# tool-board-atmega.net
KiCad netlist of a schematic drawn in EAGLE
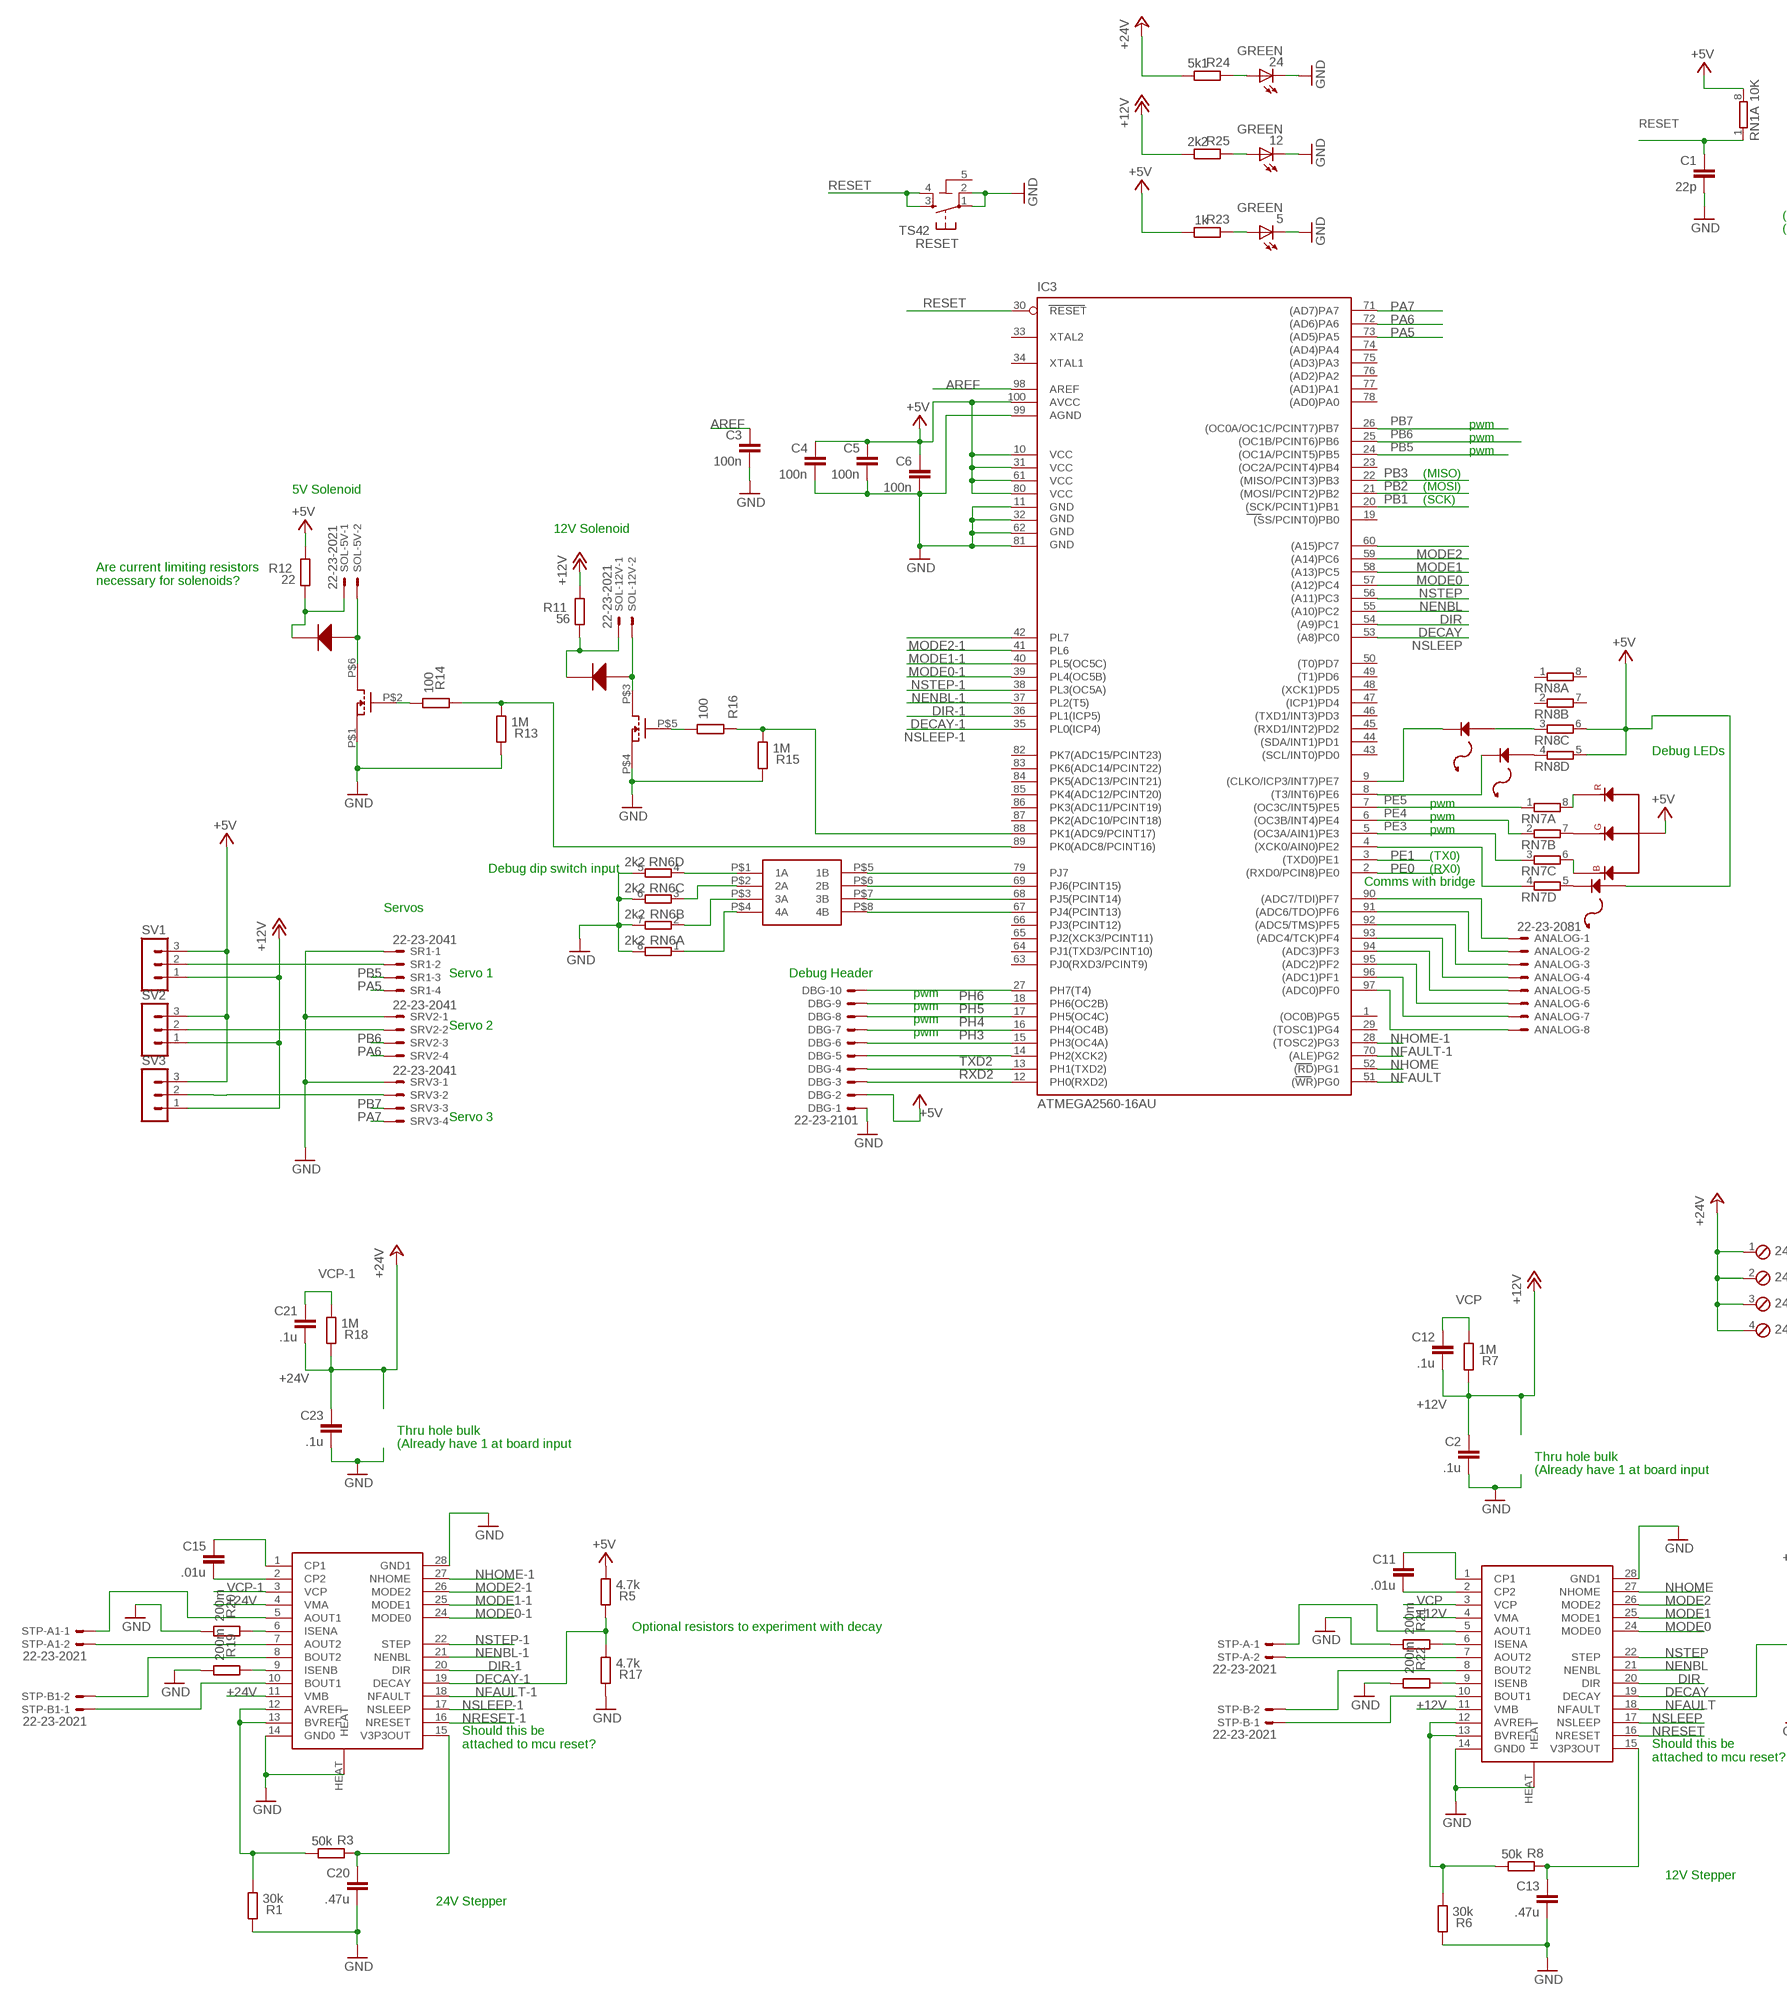
[diagram p0: schematic, sheet 1, part 1 of 2]
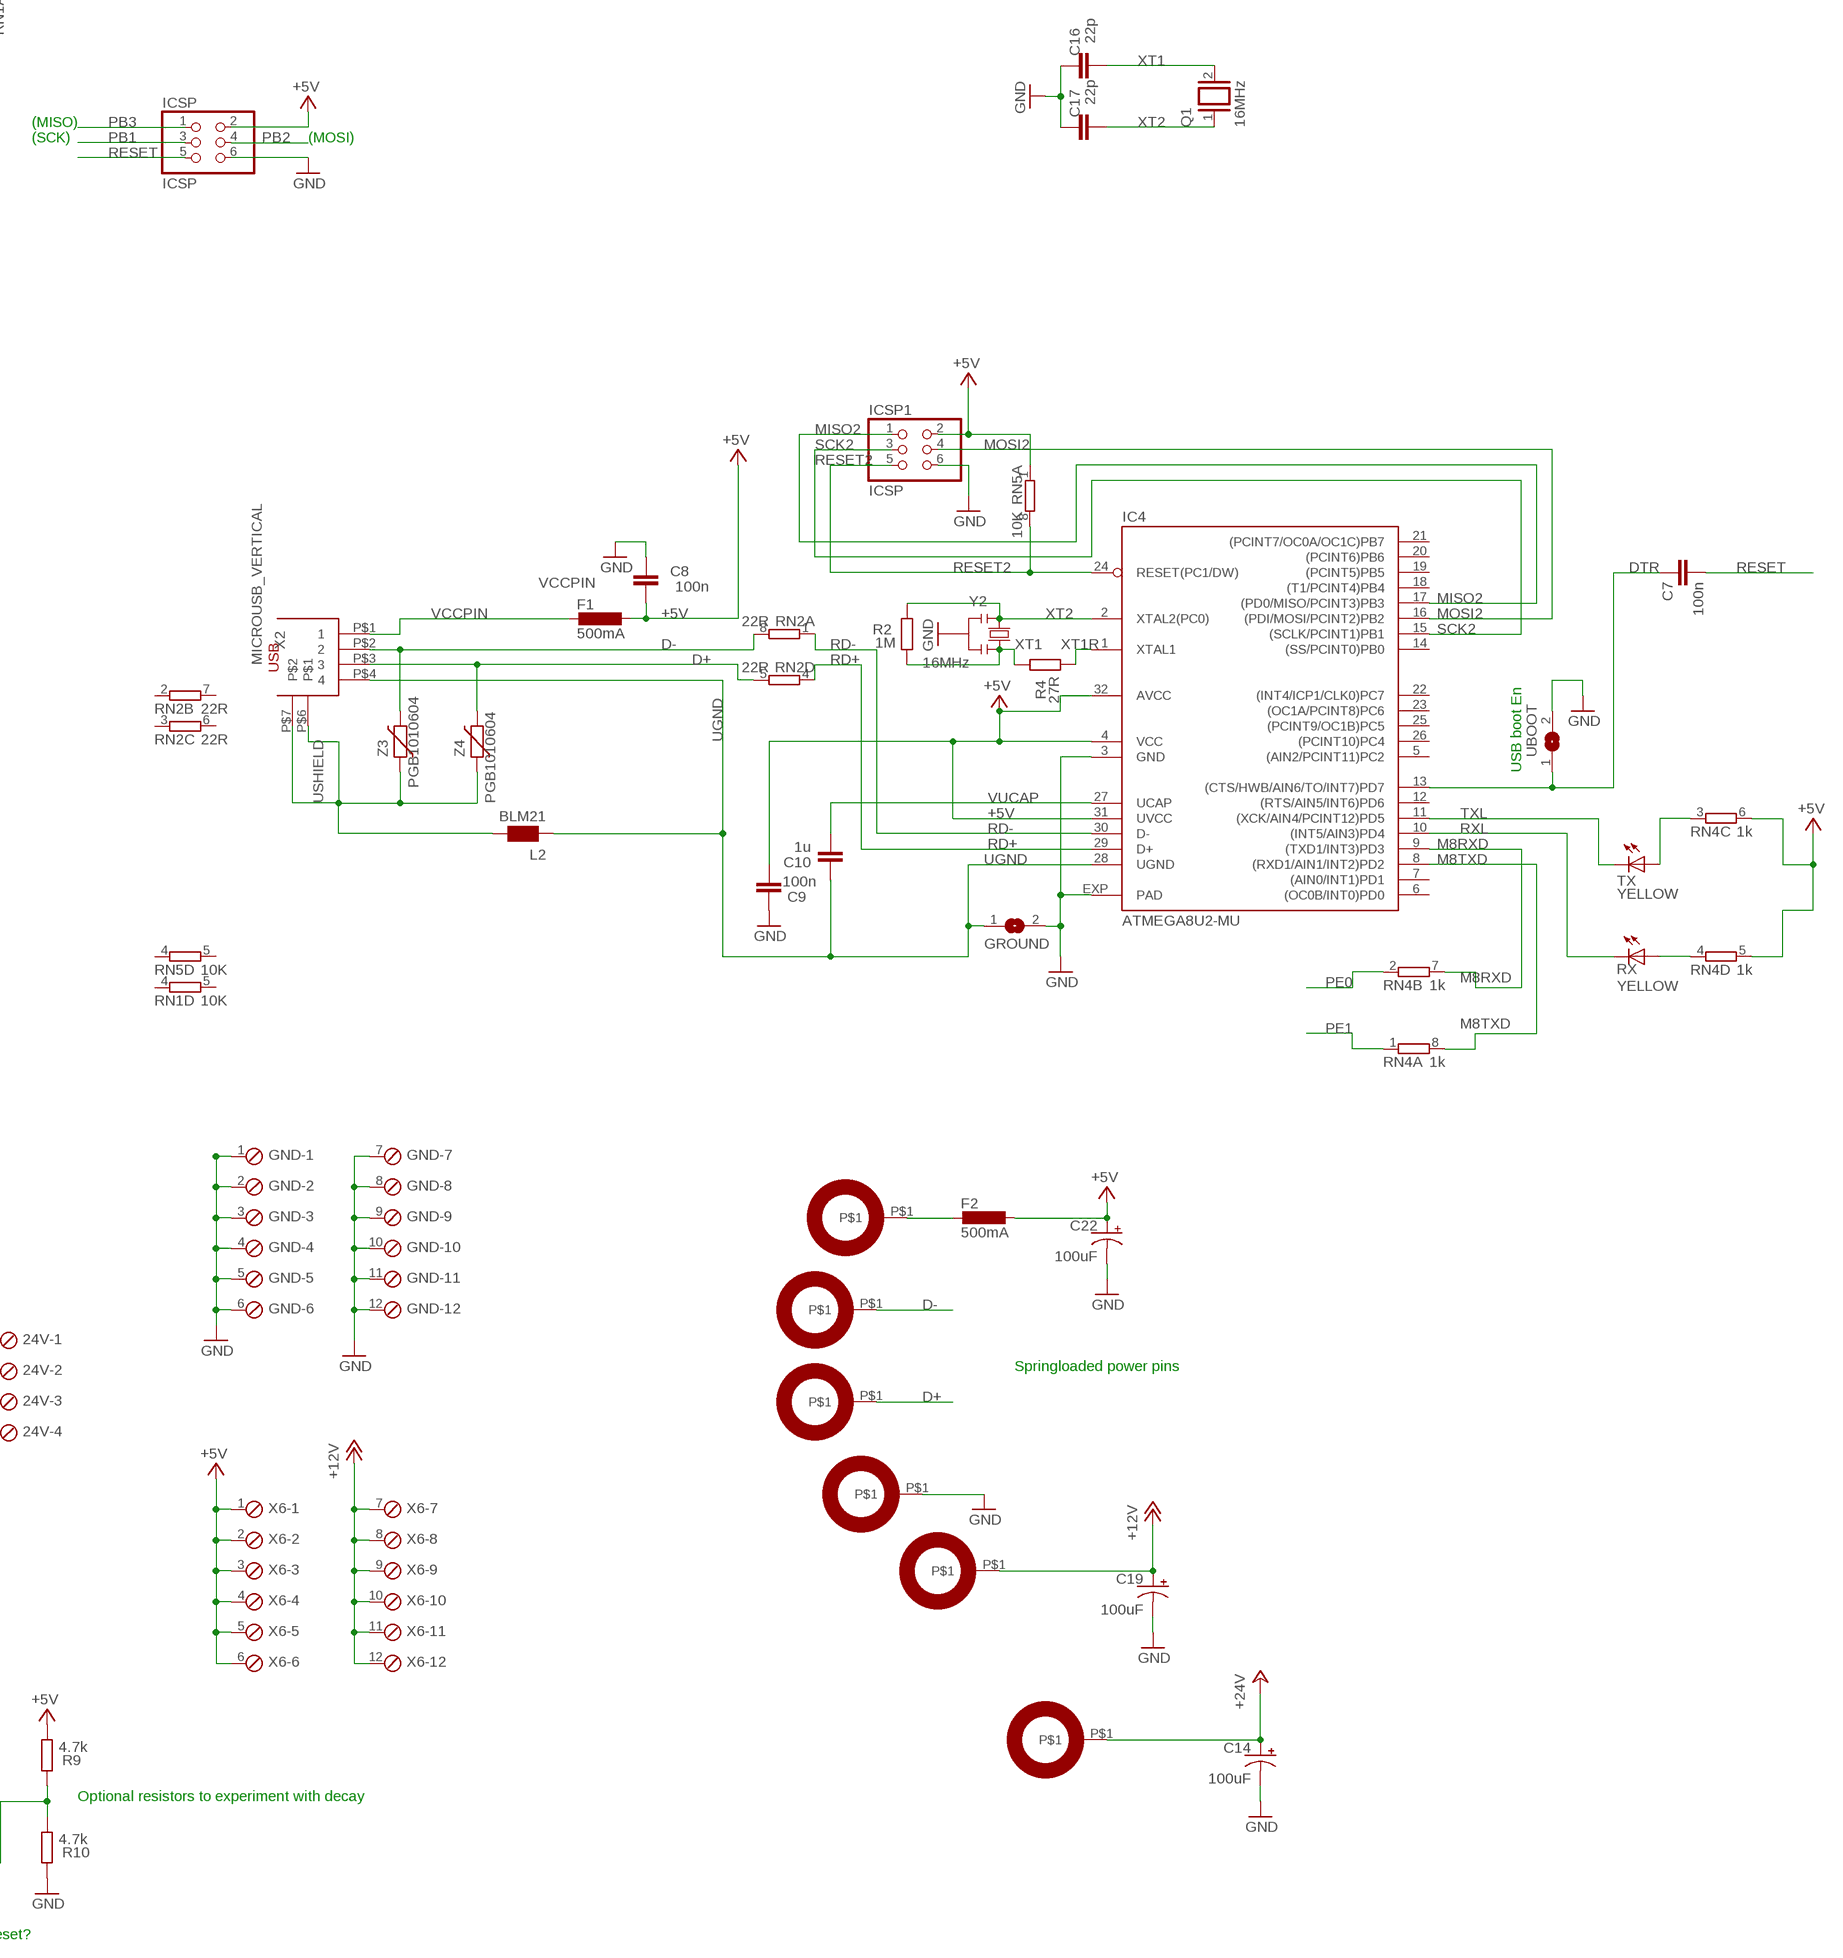
[diagram p1: schematic, sheet 1, part 2 of 2]

(export (version "E")
  (design (tool "Eeschema 10.0.6"))
  (components
    (comp (ref "5")
      (value "GREEN")
      (footprint "eagle-import:CHIP-LED0805")
      (libsource (lib "eagle-import") (part "LEDCHIP-LED0805"))
    )
    (comp (ref "12")
      (value "GREEN")
      (footprint "eagle-import:CHIP-LED0805")
      (libsource (lib "eagle-import") (part "LEDCHIP-LED0805"))
    )
    (comp (ref "24")
      (value "GREEN")
      (footprint "eagle-import:CHIP-LED0805")
      (libsource (lib "eagle-import") (part "LEDCHIP-LED0805"))
    )
    (comp (ref "24V")
      (value "MPT4")
      (footprint "eagle-import:4POL254")
      (libsource (lib "eagle-import") (part "MPT4"))
    )
    (comp (ref "ANALOG")
      (value "22-23-2081")
      (footprint "eagle-import:22-23-2081")
      (fields (field (name "MF") "MOLEX"))
      (libsource (lib "eagle-import") (part "22-23-2081"))
    )
    (comp (ref "C1")
      (value "22p")
      (footprint "eagle-import:C0603-ROUND")
      (libsource (lib "eagle-import") (part "C-EU0603-RND"))
    )
    (comp (ref "C2")
      (value ".1u")
      (footprint "eagle-import:C0603-ROUND")
      (libsource (lib "eagle-import") (part "C-EU0603-RND"))
    )
    (comp (ref "C3")
      (value "100n")
      (footprint "eagle-import:C0603-ROUND")
      (libsource (lib "eagle-import") (part "C-EU0603-RND"))
    )
    (comp (ref "C4")
      (value "100n")
      (footprint "eagle-import:C0603-ROUND")
      (libsource (lib "eagle-import") (part "C-EU0603-RND"))
    )
    (comp (ref "C5")
      (value "100n")
      (footprint "eagle-import:C0603-ROUND")
      (libsource (lib "eagle-import") (part "C-EU0603-RND"))
    )
    (comp (ref "C6")
      (value "100n")
      (footprint "eagle-import:C0603-ROUND")
      (libsource (lib "eagle-import") (part "C-EU0603-RND"))
    )
    (comp (ref "C7")
      (value "100n")
      (footprint "eagle-import:C0603-ROUND")
      (libsource (lib "eagle-import") (part "C-EU0603-RND"))
    )
    (comp (ref "C8")
      (value "100n")
      (footprint "eagle-import:C0603")
      (libsource (lib "eagle-import") (part "rcl_C-EUC0603"))
    )
    (comp (ref "C9")
      (value "100n")
      (footprint "eagle-import:C0603-ROUND")
      (libsource (lib "eagle-import") (part "C-EU0603-RND"))
    )
    (comp (ref "C10")
      (value "1u")
      (footprint "eagle-import:C0603-ROUND")
      (libsource (lib "eagle-import") (part "C-EU0603-RND"))
    )
    (comp (ref "C11")
      (value ".01u")
      (footprint "eagle-import:C0603-ROUND")
      (libsource (lib "eagle-import") (part "C-EU0603-RND"))
    )
    (comp (ref "C12")
      (value ".1u")
      (footprint "eagle-import:C0603-ROUND")
      (libsource (lib "eagle-import") (part "C-EU0603-RND"))
    )
    (comp (ref "C13")
      (value ".47u")
      (footprint "eagle-import:C0603-ROUND")
      (libsource (lib "eagle-import") (part "C-EU0603-RND"))
    )
    (comp (ref "C14")
      (value "100uF")
      (footprint "eagle-import:E3,5-8")
      (libsource (lib "eagle-import") (part "CPOL-USE3.5-8"))
    )
    (comp (ref "C15")
      (value ".01u")
      (footprint "eagle-import:C0603-ROUND")
      (libsource (lib "eagle-import") (part "C-EU0603-RND"))
    )
    (comp (ref "C16")
      (value "22p")
      (footprint "eagle-import:C0603-ROUND")
      (libsource (lib "eagle-import") (part "C-EU0603-RND"))
    )
    (comp (ref "C17")
      (value "22p")
      (footprint "eagle-import:C0603-ROUND")
      (libsource (lib "eagle-import") (part "C-EU0603-RND"))
    )
    (comp (ref "C19")
      (value "100uF")
      (footprint "eagle-import:E3,5-8")
      (libsource (lib "eagle-import") (part "CPOL-USE3.5-8"))
    )
    (comp (ref "C20")
      (value ".47u")
      (footprint "eagle-import:C0603-ROUND")
      (libsource (lib "eagle-import") (part "C-EU0603-RND"))
    )
    (comp (ref "C21")
      (value ".1u")
      (footprint "eagle-import:C0603-ROUND")
      (libsource (lib "eagle-import") (part "C-EU0603-RND"))
    )
    (comp (ref "C22")
      (value "100uF")
      (footprint "eagle-import:E3,5-8")
      (libsource (lib "eagle-import") (part "CPOL-USE3.5-8"))
    )
    (comp (ref "C23")
      (value ".1u")
      (footprint "eagle-import:C0603-ROUND")
      (libsource (lib "eagle-import") (part "C-EU0603-RND"))
    )
    (comp (ref "DBG")
      (value "22-23-2101")
      (footprint "eagle-import:22-23-2101")
      (fields (field (name "MF") "MOLEX"))
      (libsource (lib "eagle-import") (part "22-23-2101"))
    )
    (comp (ref "F1")
      (value "500mA")
      (footprint "eagle-import:L1812")
      (libsource (lib "eagle-import") (part "L-EUL1812"))
    )
    (comp (ref "F2")
      (value "500mA")
      (footprint "eagle-import:L1812")
      (libsource (lib "eagle-import") (part "L-EUL1812"))
    )
    (comp (ref "GND")
      (value "MPT12")
      (footprint "eagle-import:12POL254")
      (libsource (lib "eagle-import") (part "MPT12"))
    )
    (comp (ref "GROUND")
      (value "SJ")
      (footprint "eagle-import:SJ")
      (libsource (lib "eagle-import") (part "SJ"))
    )
    (comp (ref "IC3")
      (value "ATMEGA2560-16AU")
      (footprint "eagle-import:TQFP100")
      (libsource (lib "eagle-import") (part "ATMEGAAU1280-16"))
    )
    (comp (ref "IC4")
      (value "ATMEGA8U2-MU")
      (footprint "eagle-import:QFN32")
      (libsource (lib "eagle-import") (part "ATMEGA8U2-MU"))
    )
    (comp (ref "ICSP")
      (value "ICSP")
      (footprint "eagle-import:2X03")
      (libsource (lib "eagle-import") (part "PINHD-2X3"))
    )
    (comp (ref "ICSP1")
      (value "ICSP")
      (footprint "eagle-import:2X03")
      (libsource (lib "eagle-import") (part "PINHD-2X3"))
    )
    (comp (ref "L2")
      (value "BLM21")
      (footprint "eagle-import:0805")
      (libsource (lib "eagle-import") (part "WE-CBF_0805"))
    )
    (comp (ref "Q1")
      (value "16MHz")
      (footprint "eagle-import:QS")
      (libsource (lib "eagle-import") (part "XTAL/S"))
    )
    (comp (ref "R1")
      (value "30k")
      (footprint "eagle-import:R0603-ROUND")
      (libsource (lib "eagle-import") (part "R-EU_R0603"))
    )
    (comp (ref "R2")
      (value "1M")
      (footprint "eagle-import:R0603-ROUND")
      (libsource (lib "eagle-import") (part "R-EU_R0603"))
    )
    (comp (ref "R3")
      (value "50k")
      (footprint "eagle-import:R0603-ROUND")
      (libsource (lib "eagle-import") (part "R-EU_R0603"))
    )
    (comp (ref "R4")
      (value "27R")
      (footprint "eagle-import:R0603-ROUND")
      (libsource (lib "eagle-import") (part "R-EU_R0603"))
    )
    (comp (ref "R5")
      (value "4.7k")
      (footprint "eagle-import:R0603-ROUND")
      (libsource (lib "eagle-import") (part "R-EU_R0603"))
    )
    (comp (ref "R6")
      (value "30k")
      (footprint "eagle-import:R0603-ROUND")
      (libsource (lib "eagle-import") (part "R-EU_R0603"))
    )
    (comp (ref "R7")
      (value "1M")
      (footprint "eagle-import:R0603-ROUND")
      (libsource (lib "eagle-import") (part "R-EU_R0603"))
    )
    (comp (ref "R8")
      (value "50k")
      (footprint "eagle-import:R0603-ROUND")
      (libsource (lib "eagle-import") (part "R-EU_R0603"))
    )
    (comp (ref "R9")
      (value "4.7k")
      (footprint "eagle-import:R0603-ROUND")
      (libsource (lib "eagle-import") (part "R-EU_R0603"))
    )
    (comp (ref "R10")
      (value "4.7k")
      (footprint "eagle-import:R0603-ROUND")
      (libsource (lib "eagle-import") (part "R-EU_R0603"))
    )
    (comp (ref "R11")
      (value "56")
      (footprint "eagle-import:R0603-ROUND")
      (libsource (lib "eagle-import") (part "R-EU_R0603"))
    )
    (comp (ref "R12")
      (value "22")
      (footprint "eagle-import:R0603-ROUND")
      (libsource (lib "eagle-import") (part "R-EU_R0603"))
    )
    (comp (ref "R13")
      (value "1M")
      (footprint "eagle-import:R0603-ROUND")
      (libsource (lib "eagle-import") (part "R-EU_R0603"))
    )
    (comp (ref "R14")
      (value "100")
      (footprint "eagle-import:R0603-ROUND")
      (libsource (lib "eagle-import") (part "R-EU_R0603"))
    )
    (comp (ref "R15")
      (value "1M")
      (footprint "eagle-import:SMARTPRJ_R0603-ROUND")
      (libsource (lib "eagle-import") (part "SMARTPRJ_R-EU_0603-RND"))
    )
    (comp (ref "R16")
      (value "100")
      (footprint "eagle-import:R0603-ROUND")
      (libsource (lib "eagle-import") (part "R-EU_R0603"))
    )
    (comp (ref "R17")
      (value "4.7k")
      (footprint "eagle-import:R0603-ROUND")
      (libsource (lib "eagle-import") (part "R-EU_R0603"))
    )
    (comp (ref "R18")
      (value "1M")
      (footprint "eagle-import:R0603-ROUND")
      (libsource (lib "eagle-import") (part "R-EU_R0603"))
    )
    (comp (ref "R19")
      (value "200m")
      (footprint "eagle-import:R0603-ROUND")
      (libsource (lib "eagle-import") (part "R-EU_R0603"))
    )
    (comp (ref "R20")
      (value "200m")
      (footprint "eagle-import:R0603-ROUND")
      (libsource (lib "eagle-import") (part "R-EU_R0603"))
    )
    (comp (ref "R21")
      (value "200m")
      (footprint "eagle-import:R0603-ROUND")
      (libsource (lib "eagle-import") (part "R-EU_R0603"))
    )
    (comp (ref "R22")
      (value "200m")
      (footprint "eagle-import:R0603-ROUND")
      (libsource (lib "eagle-import") (part "R-EU_R0603"))
    )
    (comp (ref "R23")
      (value "1k")
      (footprint "eagle-import:R0603-ROUND")
      (libsource (lib "eagle-import") (part "R-EU_R0603"))
    )
    (comp (ref "R24")
      (value "5k1")
      (footprint "eagle-import:R0603-ROUND")
      (libsource (lib "eagle-import") (part "R-EU_R0603"))
    )
    (comp (ref "R25")
      (value "2k2")
      (footprint "eagle-import:R0603-ROUND")
      (libsource (lib "eagle-import") (part "R-EU_R0603"))
    )
    (comp (ref "RESET")
      (value "TS42")
      (footprint "eagle-import:TS42")
      (libsource (lib "eagle-import") (part "TS42"))
    )
    (comp (ref "RN1")
      (value "10K")
      (footprint "eagle-import:CAT16")
      (libsource (lib "eagle-import") (part "4R-NCAT16"))
    )
    (comp (ref "RN2")
      (value "22R")
      (footprint "eagle-import:CAY16")
      (libsource (lib "eagle-import") (part "4R-NCAY16"))
    )
    (comp (ref "RN4")
      (value "1k")
      (footprint "eagle-import:CAY16")
      (libsource (lib "eagle-import") (part "4R-NCAY16"))
    )
    (comp (ref "RN5")
      (value "10K")
      (footprint "eagle-import:CAT16")
      (libsource (lib "eagle-import") (part "4R-NCAT16"))
    )
    (comp (ref "RN6")
      (value "2k2")
      (footprint "eagle-import:CAY16")
      (libsource (lib "eagle-import") (part "resistor-dil_342_4R-NCAY16"))
    )
    (comp (ref "RN7")
      (value "4R-NCAY16")
      (footprint "eagle-import:CAY16")
      (libsource (lib "eagle-import") (part "resistor-dil_342_4R-NCAY16"))
    )
    (comp (ref "RN8")
      (value "4R-NCAY16")
      (footprint "eagle-import:CAY16")
      (libsource (lib "eagle-import") (part "resistor-dil_342_4R-NCAY16"))
    )
    (comp (ref "RX")
      (value "YELLOW")
      (footprint "eagle-import:CHIP-LED0805")
      (libsource (lib "eagle-import") (part "LEDCHIP-LED0805"))
    )
    (comp (ref "SOL-5V")
      (value "22-23-2021")
      (footprint "eagle-import:22-23-2021")
      (fields (field (name "MF") "MOLEX"))
      (libsource (lib "eagle-import") (part "22-23-2021"))
    )
    (comp (ref "SOL-12V")
      (value "22-23-2021")
      (footprint "eagle-import:22-23-2021")
      (fields (field (name "MF") "MOLEX"))
      (libsource (lib "eagle-import") (part "22-23-2021"))
    )
    (comp (ref "SR1")
      (value "22-23-2041")
      (footprint "eagle-import:22-23-2041")
      (fields (field (name "MF") "MOLEX"))
      (libsource (lib "eagle-import") (part "22-23-2041"))
    )
    (comp (ref "SRV2")
      (value "22-23-2041")
      (footprint "eagle-import:22-23-2041")
      (fields (field (name "MF") "MOLEX"))
      (libsource (lib "eagle-import") (part "22-23-2041"))
    )
    (comp (ref "SRV3")
      (value "22-23-2041")
      (footprint "eagle-import:22-23-2041")
      (fields (field (name "MF") "MOLEX"))
      (libsource (lib "eagle-import") (part "22-23-2041"))
    )
    (comp (ref "STP-A")
      (value "22-23-2021")
      (footprint "eagle-import:22-23-2021")
      (fields (field (name "MF") "MOLEX"))
      (libsource (lib "eagle-import") (part "22-23-2021"))
    )
    (comp (ref "STP-A1")
      (value "22-23-2021")
      (footprint "eagle-import:22-23-2021")
      (fields (field (name "MF") "MOLEX"))
      (libsource (lib "eagle-import") (part "22-23-2021"))
    )
    (comp (ref "STP-B")
      (value "22-23-2021")
      (footprint "eagle-import:22-23-2021")
      (fields (field (name "MF") "MOLEX"))
      (libsource (lib "eagle-import") (part "22-23-2021"))
    )
    (comp (ref "STP-B1")
      (value "22-23-2021")
      (footprint "eagle-import:22-23-2021")
      (fields (field (name "MF") "MOLEX"))
      (libsource (lib "eagle-import") (part "22-23-2021"))
    )
    (comp (ref "STP1")
      (value "DRV8825")
      (footprint "eagle-import:DRV8825")
      (libsource (lib "eagle-import") (part "DRV8825"))
    )
    (comp (ref "STP2")
      (value "DRV8825")
      (footprint "eagle-import:DRV8825")
      (libsource (lib "eagle-import") (part "DRV8825"))
    )
    (comp (ref "SV1")
      (value "MA03-1")
      (footprint "eagle-import:MA03-1")
      (libsource (lib "eagle-import") (part "MA03-1"))
    )
    (comp (ref "SV2")
      (value "MA03-1")
      (footprint "eagle-import:MA03-1")
      (libsource (lib "eagle-import") (part "MA03-1"))
    )
    (comp (ref "SV3")
      (value "MA03-1")
      (footprint "eagle-import:MA03-1")
      (libsource (lib "eagle-import") (part "MA03-1"))
    )
    (comp (ref "TX")
      (value "YELLOW")
      (footprint "eagle-import:CHIP-LED0805")
      (libsource (lib "eagle-import") (part "LEDCHIP-LED0805"))
    )
    (comp (ref "U$6")
      (value "SPRING_CONTACT")
      (footprint "eagle-import:SPRING_CONTACT")
      (libsource (lib "eagle-import") (part "SPRING_CONTACT"))
    )
    (comp (ref "U$8")
      (value "SMD_4P_SW")
      (footprint "eagle-import:SMD_4P_SWITCH")
      (libsource (lib "eagle-import") (part "SMD_4P_SW"))
    )
    (comp (ref "U$9")
      (value "SPRING_CONTACT")
      (footprint "eagle-import:SPRING_CONTACT")
      (libsource (lib "eagle-import") (part "SPRING_CONTACT"))
    )
    (comp (ref "U$10")
      (value "SPRING_CONTACT")
      (footprint "eagle-import:SPRING_CONTACT")
      (libsource (lib "eagle-import") (part "SPRING_CONTACT"))
    )
    (comp (ref "U$11")
      (value "SPRING_CONTACT")
      (footprint "eagle-import:SPRING_CONTACT")
      (libsource (lib "eagle-import") (part "SPRING_CONTACT"))
    )
    (comp (ref "U$12")
      (value "SPRING_CONTACT")
      (footprint "eagle-import:SPRING_CONTACT")
      (libsource (lib "eagle-import") (part "SPRING_CONTACT"))
    )
    (comp (ref "U$13")
      (value "SPRING_CONTACT")
      (footprint "eagle-import:SPRING_CONTACT")
      (libsource (lib "eagle-import") (part "SPRING_CONTACT"))
    )
    (comp (ref "U$15")
      (value "DUALNMOS-SSM6N7002KFULFCT")
      (footprint "eagle-import:SC-88")
      (libsource (lib "eagle-import") (part "DUALNMOS-SSM6N7002KFULFCT"))
    )
    (comp (ref "U$16")
      (value "0603DIODE")
      (footprint "eagle-import:SMARTPRJ_C0603-ROUND")
      (libsource (lib "eagle-import") (part "0603DIODE"))
    )
    (comp (ref "U$17")
      (value "0603DIODE")
      (footprint "eagle-import:SMARTPRJ_C0603-ROUND")
      (libsource (lib "eagle-import") (part "0603DIODE"))
    )
    (comp (ref "U$18")
      (value "RGBLED")
      (footprint "eagle-import:RGBLED")
      (libsource (lib "eagle-import") (part "RGBLED"))
    )
    (comp (ref "U$19")
      (value "0805LED")
      (footprint "eagle-import:0805LED")
      (libsource (lib "eagle-import") (part "0805LED"))
    )
    (comp (ref "U$20")
      (value "0603LED")
      (footprint "eagle-import:SMARTPRJ_C0603-ROUND")
      (libsource (lib "eagle-import") (part "0603LED"))
    )
    (comp (ref "U$21")
      (value "0603LED")
      (footprint "eagle-import:SMARTPRJ_C0603-ROUND")
      (libsource (lib "eagle-import") (part "0603LED"))
    )
    (comp (ref "UBOOT")
      (value "SJ")
      (footprint "eagle-import:SJ")
      (libsource (lib "eagle-import") (part "SJ"))
    )
    (comp (ref "X2")
      (value "MICROUSB_VERTICAL")
      (footprint "eagle-import:MICROUSB_VERT")
      (libsource (lib "eagle-import") (part "MICROUSB_VERTICAL"))
    )
    (comp (ref "X6")
      (value "MPT12")
      (footprint "eagle-import:12POL254")
      (libsource (lib "eagle-import") (part "MPT12"))
    )
    (comp (ref "Y2")
      (value "16MHz")
      (footprint "eagle-import:RESONATOR")
      (libsource (lib "eagle-import") (part "RESONATORMU"))
    )
    (comp (ref "Z3")
      (value "PGB1010604")
      (footprint "eagle-import:CT_CN0603")
      (libsource (lib "eagle-import") (part "VARISTORCN0603"))
    )
    (comp (ref "Z4")
      (value "PGB1010604")
      (footprint "eagle-import:CT_CN0603")
      (libsource (lib "eagle-import") (part "VARISTORCN0603"))
    )
  )
  (nets
    (net (code "1") (name "+5V") (class "Default")
      (node (ref "C22") (pin "+") (pinfunction "+_+") (pintype "passive"))
      (node (ref "C4") (pin "1") (pinfunction "1_1") (pintype "passive"))
      (node (ref "C5") (pin "1") (pinfunction "1_1") (pintype "passive"))
      (node (ref "C6") (pin "1") (pinfunction "1_1") (pintype "passive"))
      (node (ref "C8") (pin "1") (pinfunction "1_1") (pintype "passive"))
      (node (ref "C9") (pin "1") (pinfunction "1_1") (pintype "passive"))
      (node (ref "DBG") (pin "2") (pinfunction "S_2") (pintype "passive"))
      (node (ref "F1") (pin "1") (pinfunction "1_1") (pintype "passive"))
      (node (ref "F2") (pin "1") (pinfunction "1_1") (pintype "passive"))
      (node (ref "IC3") (pin "10") (pinfunction "VCC_10") (pintype "power_in"))
      (node (ref "IC3") (pin "100") (pinfunction "AVCC_100") (pintype "power_in"))
      (node (ref "IC3") (pin "31") (pinfunction "VCC1_31") (pintype "power_in"))
      (node (ref "IC3") (pin "61") (pinfunction "VCC2_61") (pintype "power_in"))
      (node (ref "IC3") (pin "80") (pinfunction "VCC3_80") (pintype "power_in"))
      (node (ref "IC4") (pin "31") (pinfunction "UVCC_31") (pintype "power_in"))
      (node (ref "IC4") (pin "32") (pinfunction "AVCC_32") (pintype "power_in"))
      (node (ref "IC4") (pin "4") (pinfunction "VCC_4") (pintype "power_in"))
      (node (ref "ICSP") (pin "2") (pinfunction "2_2") (pintype "passive"))
      (node (ref "ICSP1") (pin "2") (pinfunction "2_2") (pintype "passive"))
      (node (ref "R12") (pin "2") (pinfunction "2_2") (pintype "passive"))
      (node (ref "R23") (pin "1") (pinfunction "1_1") (pintype "passive"))
      (node (ref "R5") (pin "1") (pinfunction "1_1") (pintype "passive"))
      (node (ref "R9") (pin "1") (pinfunction "1_1") (pintype "passive"))
      (node (ref "RN1") (pin "8") (pinfunction "2_8") (pintype "passive"))
      (node (ref "RN4") (pin "5") (pinfunction "2_5") (pintype "passive"))
      (node (ref "RN4") (pin "6") (pinfunction "2_6") (pintype "passive"))
      (node (ref "RN5") (pin "1") (pinfunction "1_1") (pintype "passive"))
      (node (ref "RN8") (pin "5") (pinfunction "2_5") (pintype "passive"))
      (node (ref "RN8") (pin "6") (pinfunction "2_6") (pintype "passive"))
      (node (ref "SV1") (pin "3") (pinfunction "3_3") (pintype "passive"))
      (node (ref "SV2") (pin "3") (pinfunction "3_3") (pintype "passive"))
      (node (ref "SV3") (pin "3") (pinfunction "3_3") (pintype "passive"))
      (node (ref "U$18") (pin "P$4") (pinfunction "P$4_P$4") (pintype "bidirectional"))
      (node (ref "U$19") (pin "P$1") (pinfunction "A_P$1") (pintype "bidirectional"))
      (node (ref "X6") (pin "1") (pinfunction "1_1") (pintype "passive"))
      (node (ref "X6") (pin "2") (pinfunction "1_2") (pintype "passive"))
      (node (ref "X6") (pin "3") (pinfunction "1_3") (pintype "passive"))
      (node (ref "X6") (pin "4") (pinfunction "1_4") (pintype "passive"))
      (node (ref "X6") (pin "5") (pinfunction "1_5") (pintype "passive"))
      (node (ref "X6") (pin "6") (pinfunction "1_6") (pintype "passive"))
    )
    (net (code "2") (name "+12V") (class "Default")
      (node (ref "C12") (pin "2") (pinfunction "2_2") (pintype "passive"))
      (node (ref "C19") (pin "+") (pinfunction "+_+") (pintype "passive"))
      (node (ref "C2") (pin "1") (pinfunction "1_1") (pintype "passive"))
      (node (ref "R11") (pin "2") (pinfunction "2_2") (pintype "passive"))
      (node (ref "R25") (pin "1") (pinfunction "1_1") (pintype "passive"))
      (node (ref "R7") (pin "2") (pinfunction "2_2") (pintype "passive"))
      (node (ref "STP2") (pin "11") (pinfunction "VMB_11") (pintype "bidirectional"))
      (node (ref "STP2") (pin "4") (pinfunction "VMA_4") (pintype "bidirectional"))
      (node (ref "SV1") (pin "1") (pinfunction "1_1") (pintype "passive"))
      (node (ref "SV2") (pin "1") (pinfunction "1_1") (pintype "passive"))
      (node (ref "SV3") (pin "1") (pinfunction "1_1") (pintype "passive"))
      (node (ref "U$12") (pin "P$1") (pinfunction "P$1_P$1") (pintype "bidirectional"))
      (node (ref "X6") (pin "10") (pinfunction "1_10") (pintype "passive"))
      (node (ref "X6") (pin "11") (pinfunction "1_11") (pintype "passive"))
      (node (ref "X6") (pin "12") (pinfunction "1_12") (pintype "passive"))
      (node (ref "X6") (pin "7") (pinfunction "1_7") (pintype "passive"))
      (node (ref "X6") (pin "8") (pinfunction "1_8") (pintype "passive"))
      (node (ref "X6") (pin "9") (pinfunction "1_9") (pintype "passive"))
    )
    (net (code "3") (name "+24V") (class "Default")
      (node (ref "24V") (pin "1") (pinfunction "1_1") (pintype "passive"))
      (node (ref "24V") (pin "2") (pinfunction "1_2") (pintype "passive"))
      (node (ref "24V") (pin "3") (pinfunction "1_3") (pintype "passive"))
      (node (ref "24V") (pin "4") (pinfunction "1_4") (pintype "passive"))
      (node (ref "C14") (pin "+") (pinfunction "+_+") (pintype "passive"))
      (node (ref "C21") (pin "2") (pinfunction "2_2") (pintype "passive"))
      (node (ref "C23") (pin "1") (pinfunction "1_1") (pintype "passive"))
      (node (ref "R18") (pin "2") (pinfunction "2_2") (pintype "passive"))
      (node (ref "R24") (pin "1") (pinfunction "1_1") (pintype "passive"))
      (node (ref "STP1") (pin "11") (pinfunction "VMB_11") (pintype "bidirectional"))
      (node (ref "STP1") (pin "4") (pinfunction "VMA_4") (pintype "bidirectional"))
      (node (ref "U$6") (pin "P$1") (pinfunction "P$1_P$1") (pintype "bidirectional"))
    )
    (net (code "4") (name "/5-GND") (class "Default")
      (node (ref "RESET") (pin "5") (pinfunction "5-GND_5") (pintype "power_in"))
    )
    (net (code "5") (name "/AREF") (class "Default")
      (node (ref "C3") (pin "1") (pinfunction "1_1") (pintype "passive"))
      (node (ref "IC3") (pin "98") (pinfunction "AREF_98") (pintype "bidirectional"))
    )
    (net (code "6") (name "/D+") (class "Default")
      (node (ref "RN2") (pin "5") (pinfunction "2_5") (pintype "passive"))
      (node (ref "U$13") (pin "P$1") (pinfunction "P$1_P$1") (pintype "bidirectional"))
      (node (ref "X2") (pin "P$3") (pinfunction "3_P$3") (pintype "bidirectional"))
      (node (ref "Z4") (pin "2") (pinfunction "2_2") (pintype "passive"))
    )
    (net (code "7") (name "/D-") (class "Default")
      (node (ref "RN2") (pin "8") (pinfunction "2_8") (pintype "passive"))
      (node (ref "U$10") (pin "P$1") (pinfunction "P$1_P$1") (pintype "bidirectional"))
      (node (ref "X2") (pin "P$2") (pinfunction "2_P$2") (pintype "bidirectional"))
      (node (ref "Z3") (pin "2") (pinfunction "2_2") (pintype "passive"))
    )
    (net (code "8") (name "/DECAY") (class "Default")
      (node (ref "IC3") (pin "54") (pinfunction "(A9)PC1_54") (pintype "bidirectional"))
      (node (ref "R10") (pin "1") (pinfunction "1_1") (pintype "passive"))
      (node (ref "R9") (pin "2") (pinfunction "2_2") (pintype "passive"))
      (node (ref "STP2") (pin "19") (pinfunction "DECAY_19") (pintype "bidirectional"))
    )
    (net (code "9") (name "/DECAY-1") (class "Default")
      (node (ref "IC3") (pin "36") (pinfunction "PL1(ICP5)_36") (pintype "bidirectional"))
      (node (ref "R17") (pin "1") (pinfunction "1_1") (pintype "passive"))
      (node (ref "R5") (pin "2") (pinfunction "2_2") (pintype "passive"))
      (node (ref "STP1") (pin "19") (pinfunction "DECAY_19") (pintype "bidirectional"))
    )
    (net (code "10") (name "/DIR") (class "Default")
      (node (ref "IC3") (pin "55") (pinfunction "(A10)PC2_55") (pintype "bidirectional"))
      (node (ref "STP2") (pin "20") (pinfunction "DIR_20") (pintype "bidirectional"))
    )
    (net (code "11") (name "/DIR-1") (class "Default")
      (node (ref "IC3") (pin "37") (pinfunction "PL2(T5)_37") (pintype "bidirectional"))
      (node (ref "STP1") (pin "20") (pinfunction "DIR_20") (pintype "bidirectional"))
    )
    (net (code "12") (name "/DTR") (class "Default")
      (node (ref "C7") (pin "1") (pinfunction "1_1") (pintype "passive"))
      (node (ref "IC4") (pin "13") (pinfunction "(CTS/HWB/AIN6/TO/INT7)PD7_13") (pintype "bidirectional"))
      (node (ref "UBOOT") (pin "1") (pinfunction "1_1") (pintype "passive"))
    )
    (net (code "13") (name "/M8RXD") (class "Default")
      (node (ref "IC4") (pin "9") (pinfunction "(TXD1/INT3)PD3_9") (pintype "bidirectional"))
      (node (ref "RN4") (pin "7") (pinfunction "2_7") (pintype "passive"))
    )
    (net (code "14") (name "/M8TXD") (class "Default")
      (node (ref "IC4") (pin "8") (pinfunction "(RXD1/AIN1/INT2)PD2_8") (pintype "bidirectional"))
      (node (ref "RN4") (pin "8") (pinfunction "2_8") (pintype "passive"))
    )
    (net (code "15") (name "/MISO2") (class "Default")
      (node (ref "IC4") (pin "17") (pinfunction "(PD0/MISO/PCINT3)PB3_17") (pintype "bidirectional"))
      (node (ref "ICSP1") (pin "1") (pinfunction "1_1") (pintype "passive"))
    )
    (net (code "16") (name "/MODE0") (class "Default")
      (node (ref "IC3") (pin "58") (pinfunction "(A13)PC5_58") (pintype "bidirectional"))
      (node (ref "STP2") (pin "24") (pinfunction "MODE0_24") (pintype "bidirectional"))
    )
    (net (code "17") (name "/MODE0-1") (class "Default")
      (node (ref "IC3") (pin "40") (pinfunction "PL5(OC5C)_40") (pintype "bidirectional"))
      (node (ref "STP1") (pin "24") (pinfunction "MODE0_24") (pintype "bidirectional"))
    )
    (net (code "18") (name "/MODE1") (class "Default")
      (node (ref "IC3") (pin "59") (pinfunction "(A14)PC6_59") (pintype "bidirectional"))
      (node (ref "STP2") (pin "25") (pinfunction "MODE1_25") (pintype "bidirectional"))
    )
    (net (code "19") (name "/MODE1-1") (class "Default")
      (node (ref "IC3") (pin "41") (pinfunction "PL6_41") (pintype "bidirectional"))
      (node (ref "STP1") (pin "25") (pinfunction "MODE1_25") (pintype "bidirectional"))
    )
    (net (code "20") (name "/MODE2") (class "Default")
      (node (ref "IC3") (pin "60") (pinfunction "(A15)PC7_60") (pintype "bidirectional"))
      (node (ref "STP2") (pin "26") (pinfunction "MODE2_26") (pintype "bidirectional"))
    )
    (net (code "21") (name "/MODE2-1") (class "Default")
      (node (ref "IC3") (pin "42") (pinfunction "PL7_42") (pintype "bidirectional"))
      (node (ref "STP1") (pin "26") (pinfunction "MODE2_26") (pintype "bidirectional"))
    )
    (net (code "22") (name "/MOSI2") (class "Default")
      (node (ref "IC4") (pin "16") (pinfunction "(PDI/MOSI/PCINT2)PB2_16") (pintype "bidirectional"))
      (node (ref "ICSP1") (pin "4") (pinfunction "4_4") (pintype "passive"))
    )
    (net (code "23") (name "/NENBL") (class "Default")
      (node (ref "IC3") (pin "56") (pinfunction "(A11)PC3_56") (pintype "bidirectional"))
      (node (ref "STP2") (pin "21") (pinfunction "NENBL_21") (pintype "bidirectional"))
    )
    (net (code "24") (name "/NENBL-1") (class "Default")
      (node (ref "IC3") (pin "38") (pinfunction "PL3(OC5A)_38") (pintype "bidirectional"))
      (node (ref "STP1") (pin "21") (pinfunction "NENBL_21") (pintype "bidirectional"))
    )
    (net (code "25") (name "/NFAULT") (class "Default")
      (node (ref "IC3") (pin "51") (pinfunction "(WR)PG0_51") (pintype "bidirectional"))
      (node (ref "STP2") (pin "18") (pinfunction "NFAULT_18") (pintype "bidirectional"))
    )
    (net (code "26") (name "/NFAULT-1") (class "Default")
      (node (ref "IC3") (pin "70") (pinfunction "(ALE)PG2_70") (pintype "bidirectional"))
      (node (ref "STP1") (pin "18") (pinfunction "NFAULT_18") (pintype "bidirectional"))
    )
    (net (code "27") (name "/NHOME") (class "Default")
      (node (ref "IC3") (pin "52") (pinfunction "(RD)PG1_52") (pintype "bidirectional"))
      (node (ref "STP2") (pin "27") (pinfunction "NHOME_27") (pintype "bidirectional"))
    )
    (net (code "28") (name "/NHOME-1") (class "Default")
      (node (ref "IC3") (pin "28") (pinfunction "(TOSC2)PG3_28") (pintype "bidirectional"))
      (node (ref "STP1") (pin "27") (pinfunction "NHOME_27") (pintype "bidirectional"))
    )
    (net (code "29") (name "/NRESET") (class "Default")
      (node (ref "STP2") (pin "16") (pinfunction "NRESET_16") (pintype "bidirectional"))
    )
    (net (code "30") (name "/NRESET-1") (class "Default")
      (node (ref "STP1") (pin "16") (pinfunction "NRESET_16") (pintype "bidirectional"))
    )
    (net (code "31") (name "/NSLEEP") (class "Default")
      (node (ref "IC3") (pin "53") (pinfunction "(A8)PC0_53") (pintype "bidirectional"))
      (node (ref "STP2") (pin "17") (pinfunction "NSLEEP_17") (pintype "bidirectional"))
    )
    (net (code "32") (name "/NSLEEP-1") (class "Default")
      (node (ref "IC3") (pin "35") (pinfunction "PL0(ICP4)_35") (pintype "bidirectional"))
      (node (ref "STP1") (pin "17") (pinfunction "NSLEEP_17") (pintype "bidirectional"))
    )
    (net (code "33") (name "/NSTEP") (class "Default")
      (node (ref "IC3") (pin "57") (pinfunction "(A12)PC4_57") (pintype "bidirectional"))
      (node (ref "STP2") (pin "22") (pinfunction "STEP_22") (pintype "bidirectional"))
    )
    (net (code "34") (name "/NSTEP-1") (class "Default")
      (node (ref "IC3") (pin "39") (pinfunction "PL4(OC5B)_39") (pintype "bidirectional"))
      (node (ref "STP1") (pin "22") (pinfunction "STEP_22") (pintype "bidirectional"))
    )
    (net (code "35") (name "/PA5") (class "Default")
      (node (ref "IC3") (pin "73") (pinfunction "(AD5)PA5_73") (pintype "bidirectional"))
      (node (ref "SR1") (pin "4") (pinfunction "S_4") (pintype "passive"))
    )
    (net (code "36") (name "/PA6") (class "Default")
      (node (ref "IC3") (pin "72") (pinfunction "(AD6)PA6_72") (pintype "bidirectional"))
      (node (ref "SRV2") (pin "4") (pinfunction "S_4") (pintype "passive"))
    )
    (net (code "37") (name "/PA7") (class "Default")
      (node (ref "IC3") (pin "71") (pinfunction "(AD7)PA7_71") (pintype "bidirectional"))
      (node (ref "SRV3") (pin "4") (pinfunction "S_4") (pintype "passive"))
    )
    (net (code "38") (name "/PB1") (class "Default")
      (node (ref "IC3") (pin "20") (pinfunction "(SCK/PCINT1)PB1_20") (pintype "bidirectional"))
      (node (ref "ICSP") (pin "3") (pinfunction "3_3") (pintype "passive"))
    )
    (net (code "39") (name "/PB2") (class "Default")
      (node (ref "IC3") (pin "21") (pinfunction "(MOSI/PCINT2)PB2_21") (pintype "bidirectional"))
      (node (ref "ICSP") (pin "4") (pinfunction "4_4") (pintype "passive"))
    )
    (net (code "40") (name "/PB3") (class "Default")
      (node (ref "IC3") (pin "22") (pinfunction "(MISO/PCINT3)PB3_22") (pintype "bidirectional"))
      (node (ref "ICSP") (pin "1") (pinfunction "1_1") (pintype "passive"))
    )
    (net (code "41") (name "/PB5") (class "Default")
      (node (ref "IC3") (pin "24") (pinfunction "(OC1A/PCINT5)PB5_24") (pintype "bidirectional"))
      (node (ref "SR1") (pin "3") (pinfunction "S_3") (pintype "passive"))
    )
    (net (code "42") (name "/PB6") (class "Default")
      (node (ref "IC3") (pin "25") (pinfunction "(OC1B/PCINT6)PB6_25") (pintype "bidirectional"))
      (node (ref "SRV2") (pin "3") (pinfunction "S_3") (pintype "passive"))
    )
    (net (code "43") (name "/PB7") (class "Default")
      (node (ref "IC3") (pin "26") (pinfunction "(OC0A/OC1C/PCINT7)PB7_26") (pintype "bidirectional"))
      (node (ref "SRV3") (pin "3") (pinfunction "S_3") (pintype "passive"))
    )
    (net (code "44") (name "/PE0") (class "Default")
      (node (ref "IC3") (pin "2") (pinfunction "(RXD0/PCIN8)PE0_2") (pintype "bidirectional"))
      (node (ref "RN4") (pin "2") (pinfunction "1_2") (pintype "passive"))
    )
    (net (code "45") (name "/PE1") (class "Default")
      (node (ref "IC3") (pin "3") (pinfunction "(TXD0)PE1_3") (pintype "bidirectional"))
      (node (ref "RN4") (pin "1") (pinfunction "1_1") (pintype "passive"))
    )
    (net (code "46") (name "/PE3") (class "Default")
      (node (ref "IC3") (pin "5") (pinfunction "(OC3A/AIN1)PE3_5") (pintype "bidirectional"))
      (node (ref "RN7") (pin "3") (pinfunction "1_3") (pintype "passive"))
    )
    (net (code "47") (name "/PE4") (class "Default")
      (node (ref "IC3") (pin "6") (pinfunction "(OC3B/INT4)PE4_6") (pintype "bidirectional"))
      (node (ref "RN7") (pin "2") (pinfunction "1_2") (pintype "passive"))
    )
    (net (code "48") (name "/PE5") (class "Default")
      (node (ref "IC3") (pin "7") (pinfunction "(OC3C/INT5)PE5_7") (pintype "bidirectional"))
      (node (ref "RN7") (pin "1") (pinfunction "1_1") (pintype "passive"))
    )
    (net (code "49") (name "/PH3") (class "Default")
      (node (ref "DBG") (pin "6") (pinfunction "S_6") (pintype "passive"))
      (node (ref "IC3") (pin "15") (pinfunction "PH3(OC4A)_15") (pintype "bidirectional"))
    )
    (net (code "50") (name "/PH4") (class "Default")
      (node (ref "DBG") (pin "7") (pinfunction "S_7") (pintype "passive"))
      (node (ref "IC3") (pin "16") (pinfunction "PH4(OC4B)_16") (pintype "bidirectional"))
    )
    (net (code "51") (name "/PH5") (class "Default")
      (node (ref "DBG") (pin "8") (pinfunction "S_8") (pintype "passive"))
      (node (ref "IC3") (pin "17") (pinfunction "PH5(OC4C)_17") (pintype "bidirectional"))
    )
    (net (code "52") (name "/PH6") (class "Default")
      (node (ref "DBG") (pin "9") (pinfunction "S_9") (pintype "passive"))
      (node (ref "IC3") (pin "18") (pinfunction "PH6(OC2B)_18") (pintype "bidirectional"))
    )
    (net (code "53") (name "/RD+") (class "Default")
      (node (ref "IC4") (pin "29") (pinfunction "D+_29") (pintype "bidirectional"))
      (node (ref "RN2") (pin "4") (pinfunction "1_4") (pintype "passive"))
    )
    (net (code "54") (name "/RD-") (class "Default")
      (node (ref "IC4") (pin "30") (pinfunction "D-_30") (pintype "bidirectional"))
      (node (ref "RN2") (pin "1") (pinfunction "1_1") (pintype "passive"))
    )
    (net (code "55") (name "/RESET") (class "Default")
      (node (ref "C1") (pin "1") (pinfunction "1_1") (pintype "passive"))
      (node (ref "C7") (pin "2") (pinfunction "2_2") (pintype "passive"))
      (node (ref "IC3") (pin "30") (pinfunction "RESET_30") (pintype "input"))
      (node (ref "ICSP") (pin "5") (pinfunction "5_5") (pintype "passive"))
      (node (ref "RESET") (pin "3") (pinfunction "3_3") (pintype "passive"))
      (node (ref "RESET") (pin "4") (pinfunction "4_4") (pintype "passive"))
      (node (ref "RN1") (pin "1") (pinfunction "1_1") (pintype "passive"))
    )
    (net (code "56") (name "/RESET2") (class "Default")
      (node (ref "IC4") (pin "24") (pinfunction "RESET(PC1/DW)_24") (pintype "input"))
      (node (ref "ICSP1") (pin "5") (pinfunction "5_5") (pintype "passive"))
      (node (ref "RN5") (pin "8") (pinfunction "2_8") (pintype "passive"))
    )
    (net (code "57") (name "/RXD2") (class "Default")
      (node (ref "DBG") (pin "3") (pinfunction "S_3") (pintype "passive"))
      (node (ref "IC3") (pin "12") (pinfunction "PH0(RXD2)_12") (pintype "bidirectional"))
    )
    (net (code "58") (name "/RXL") (class "Default")
      (node (ref "IC4") (pin "10") (pinfunction "(INT5/AIN3)PD4_10") (pintype "bidirectional"))
      (node (ref "RX") (pin "C") (pinfunction "C_C") (pintype "passive"))
    )
    (net (code "59") (name "/SCK2") (class "Default")
      (node (ref "IC4") (pin "15") (pinfunction "(SCLK/PCINT1)PB1_15") (pintype "bidirectional"))
      (node (ref "ICSP1") (pin "3") (pinfunction "3_3") (pintype "passive"))
    )
    (net (code "60") (name "/TXD2") (class "Default")
      (node (ref "DBG") (pin "4") (pinfunction "S_4") (pintype "passive"))
      (node (ref "IC3") (pin "13") (pinfunction "PH1(TXD2)_13") (pintype "bidirectional"))
    )
    (net (code "61") (name "/TXL") (class "Default")
      (node (ref "IC4") (pin "11") (pinfunction "(XCK/AIN4/PCINT12)PD5_11") (pintype "bidirectional"))
      (node (ref "TX") (pin "C") (pinfunction "C_C") (pintype "passive"))
    )
    (net (code "62") (name "/UGND") (class "Default")
      (node (ref "C10") (pin "2") (pinfunction "2_2") (pintype "passive"))
      (node (ref "GROUND") (pin "1") (pinfunction "1_1") (pintype "passive"))
      (node (ref "IC4") (pin "28") (pinfunction "UGND_28") (pintype "power_in"))
      (node (ref "L2") (pin "1") (pinfunction "1_1") (pintype "passive"))
      (node (ref "X2") (pin "P$4") (pinfunction "4_P$4") (pintype "bidirectional"))
    )
    (net (code "63") (name "/USHIELD") (class "Default")
      (node (ref "L2") (pin "2") (pinfunction "2_2") (pintype "passive"))
      (node (ref "X2") (pin "P$6") (pinfunction "P$1_P$6") (pintype "bidirectional"))
      (node (ref "X2") (pin "P$7") (pinfunction "P$2_P$7") (pintype "bidirectional"))
      (node (ref "Z3") (pin "1") (pinfunction "1_1") (pintype "passive"))
      (node (ref "Z4") (pin "1") (pinfunction "1_1") (pintype "passive"))
    )
    (net (code "64") (name "/VCCPIN") (class "Default")
      (node (ref "F1") (pin "2") (pinfunction "2_2") (pintype "passive"))
      (node (ref "X2") (pin "P$1") (pinfunction "1_P$1") (pintype "bidirectional"))
    )
    (net (code "65") (name "/VCP") (class "Default")
      (node (ref "C12") (pin "1") (pinfunction "1_1") (pintype "passive"))
      (node (ref "R7") (pin "1") (pinfunction "1_1") (pintype "passive"))
      (node (ref "STP2") (pin "3") (pinfunction "VCP_3") (pintype "bidirectional"))
    )
    (net (code "66") (name "/VCP-1") (class "Default")
      (node (ref "C21") (pin "1") (pinfunction "1_1") (pintype "passive"))
      (node (ref "R18") (pin "1") (pinfunction "1_1") (pintype "passive"))
      (node (ref "STP1") (pin "3") (pinfunction "VCP_3") (pintype "bidirectional"))
    )
    (net (code "67") (name "/VUCAP") (class "Default")
      (node (ref "C10") (pin "1") (pinfunction "1_1") (pintype "passive"))
      (node (ref "IC4") (pin "27") (pinfunction "UCAP_27") (pintype "passive"))
    )
    (net (code "68") (name "/XT1") (class "Default")
      (node (ref "C16") (pin "1") (pinfunction "1_1") (pintype "passive"))
      (node (ref "Q1") (pin "2") (pinfunction "2_2") (pintype "passive"))
      (node (ref "R2") (pin "1") (pinfunction "1_1") (pintype "passive"))
      (node (ref "R4") (pin "2") (pinfunction "2_2") (pintype "passive"))
      (node (ref "Y2") (pin "3") (pinfunction "3_3") (pintype "passive"))
    )
    (net (code "69") (name "/XT1R") (class "Default")
      (node (ref "IC4") (pin "1") (pinfunction "XTAL1_1") (pintype "bidirectional"))
      (node (ref "R4") (pin "1") (pinfunction "1_1") (pintype "passive"))
    )
    (net (code "70") (name "/XT2") (class "Default")
      (node (ref "C17") (pin "1") (pinfunction "1_1") (pintype "passive"))
      (node (ref "IC4") (pin "2") (pinfunction "XTAL2(PC0)_2") (pintype "bidirectional"))
      (node (ref "Q1") (pin "1") (pinfunction "1_1") (pintype "passive"))
      (node (ref "R2") (pin "2") (pinfunction "2_2") (pintype "passive"))
      (node (ref "Y2") (pin "1") (pinfunction "1_1") (pintype "passive"))
    )
    (net (code "71") (name "GND") (class "Default")
      (node (ref "12") (pin "C") (pinfunction "C_C") (pintype "passive"))
      (node (ref "24") (pin "C") (pinfunction "C_C") (pintype "passive"))
      (node (ref "5") (pin "C") (pinfunction "C_C") (pintype "passive"))
      (node (ref "C1") (pin "2") (pinfunction "2_2") (pintype "passive"))
      (node (ref "C13") (pin "2") (pinfunction "2_2") (pintype "passive"))
      (node (ref "C14") (pin "-") (pinfunction "-_-") (pintype "passive"))
      (node (ref "C16") (pin "2") (pinfunction "2_2") (pintype "passive"))
      (node (ref "C17") (pin "2") (pinfunction "2_2") (pintype "passive"))
      (node (ref "C19") (pin "-") (pinfunction "-_-") (pintype "passive"))
      (node (ref "C2") (pin "2") (pinfunction "2_2") (pintype "passive"))
      (node (ref "C20") (pin "2") (pinfunction "2_2") (pintype "passive"))
      (node (ref "C22") (pin "-") (pinfunction "-_-") (pintype "passive"))
      (node (ref "C23") (pin "2") (pinfunction "2_2") (pintype "passive"))
      (node (ref "C3") (pin "2") (pinfunction "2_2") (pintype "passive"))
      (node (ref "C4") (pin "2") (pinfunction "2_2") (pintype "passive"))
      (node (ref "C5") (pin "2") (pinfunction "2_2") (pintype "passive"))
      (node (ref "C6") (pin "2") (pinfunction "2_2") (pintype "passive"))
      (node (ref "C8") (pin "2") (pinfunction "2_2") (pintype "passive"))
      (node (ref "C9") (pin "2") (pinfunction "2_2") (pintype "passive"))
      (node (ref "DBG") (pin "1") (pinfunction "S_1") (pintype "passive"))
      (node (ref "GND") (pin "1") (pinfunction "1_1") (pintype "passive"))
      (node (ref "GND") (pin "10") (pinfunction "1_10") (pintype "passive"))
      (node (ref "GND") (pin "11") (pinfunction "1_11") (pintype "passive"))
      (node (ref "GND") (pin "12") (pinfunction "1_12") (pintype "passive"))
      (node (ref "GND") (pin "2") (pinfunction "1_2") (pintype "passive"))
      (node (ref "GND") (pin "3") (pinfunction "1_3") (pintype "passive"))
      (node (ref "GND") (pin "4") (pinfunction "1_4") (pintype "passive"))
      (node (ref "GND") (pin "5") (pinfunction "1_5") (pintype "passive"))
      (node (ref "GND") (pin "6") (pinfunction "1_6") (pintype "passive"))
      (node (ref "GND") (pin "7") (pinfunction "1_7") (pintype "passive"))
      (node (ref "GND") (pin "8") (pinfunction "1_8") (pintype "passive"))
      (node (ref "GND") (pin "9") (pinfunction "1_9") (pintype "passive"))
      (node (ref "GROUND") (pin "2") (pinfunction "2_2") (pintype "passive"))
      (node (ref "IC3") (pin "11") (pinfunction "GND_11") (pintype "power_in"))
      (node (ref "IC3") (pin "32") (pinfunction "GND1_32") (pintype "power_in"))
      (node (ref "IC3") (pin "62") (pinfunction "GND2_62") (pintype "power_in"))
      (node (ref "IC3") (pin "81") (pinfunction "GND3_81") (pintype "power_in"))
      (node (ref "IC3") (pin "99") (pinfunction "AGND_99") (pintype "power_in"))
      (node (ref "IC4") (pin "3") (pinfunction "GND_3") (pintype "power_in"))
      (node (ref "IC4") (pin "EXP") (pinfunction "PAD_EXP") (pintype "power_in"))
      (node (ref "ICSP") (pin "6") (pinfunction "6_6") (pintype "passive"))
      (node (ref "ICSP1") (pin "6") (pinfunction "6_6") (pintype "passive"))
      (node (ref "R1") (pin "2") (pinfunction "2_2") (pintype "passive"))
      (node (ref "R10") (pin "2") (pinfunction "2_2") (pintype "passive"))
      (node (ref "R13") (pin "2") (pinfunction "2_2") (pintype "passive"))
      (node (ref "R15") (pin "2") (pinfunction "2_2") (pintype "passive"))
      (node (ref "R17") (pin "2") (pinfunction "2_2") (pintype "passive"))
      (node (ref "R19") (pin "1") (pinfunction "1_1") (pintype "passive"))
      (node (ref "R20") (pin "1") (pinfunction "1_1") (pintype "passive"))
      (node (ref "R21") (pin "1") (pinfunction "1_1") (pintype "passive"))
      (node (ref "R22") (pin "1") (pinfunction "1_1") (pintype "passive"))
      (node (ref "R6") (pin "2") (pinfunction "2_2") (pintype "passive"))
      (node (ref "RESET") (pin "1") (pinfunction "1_1") (pintype "passive"))
      (node (ref "RESET") (pin "2") (pinfunction "2_2") (pintype "passive"))
      (node (ref "RN6") (pin "5") (pinfunction "2_5") (pintype "passive"))
      (node (ref "RN6") (pin "6") (pinfunction "2_6") (pintype "passive"))
      (node (ref "RN6") (pin "7") (pinfunction "2_7") (pintype "passive"))
      (node (ref "RN6") (pin "8") (pinfunction "2_8") (pintype "passive"))
      (node (ref "SR1") (pin "1") (pinfunction "S_1") (pintype "passive"))
      (node (ref "SRV2") (pin "1") (pinfunction "S_1") (pintype "passive"))
      (node (ref "SRV3") (pin "1") (pinfunction "S_1") (pintype "passive"))
      (node (ref "STP1") (pin "14") (pinfunction "GND0_14") (pintype "power_in"))
      (node (ref "STP1") (pin "28") (pinfunction "GND1_28") (pintype "power_in"))
      (node (ref "STP1") (pin "HEAT") (pinfunction "HEAT_HEAT") (pintype "bidirectional"))
      (node (ref "STP2") (pin "14") (pinfunction "GND0_14") (pintype "power_in"))
      (node (ref "STP2") (pin "28") (pinfunction "GND1_28") (pintype "power_in"))
      (node (ref "STP2") (pin "HEAT") (pinfunction "HEAT_HEAT") (pintype "bidirectional"))
      (node (ref "U$11") (pin "P$1") (pinfunction "P$1_P$1") (pintype "bidirectional"))
      (node (ref "U$15") (pin "P$1") (pinfunction "S_P$1") (pintype "bidirectional"))
      (node (ref "U$15") (pin "P$4") (pinfunction "S_P$4") (pintype "bidirectional"))
      (node (ref "UBOOT") (pin "2") (pinfunction "2_2") (pintype "passive"))
      (node (ref "Y2") (pin "2") (pinfunction "2_2") (pintype "passive"))
    )
    (net (code "72") (name "Net-(5-PadA)") (class "Default")
      (node (ref "5") (pin "A") (pinfunction "A_A") (pintype "passive"))
      (node (ref "R23") (pin "2") (pinfunction "2_2") (pintype "passive"))
    )
    (net (code "73") (name "Net-(12-PadA)") (class "Default")
      (node (ref "12") (pin "A") (pinfunction "A_A") (pintype "passive"))
      (node (ref "R25") (pin "2") (pinfunction "2_2") (pintype "passive"))
    )
    (net (code "74") (name "Net-(24-PadA)") (class "Default")
      (node (ref "24") (pin "A") (pinfunction "A_A") (pintype "passive"))
      (node (ref "R24") (pin "2") (pinfunction "2_2") (pintype "passive"))
    )
    (net (code "75") (name "Net-(ANALOGA-S)") (class "Default")
      (node (ref "ANALOG") (pin "1") (pinfunction "S_1") (pintype "passive"))
      (node (ref "IC3") (pin "90") (pinfunction "(ADC7/TDI)PF7_90") (pintype "bidirectional"))
    )
    (net (code "76") (name "Net-(ANALOGB-S)") (class "Default")
      (node (ref "ANALOG") (pin "2") (pinfunction "S_2") (pintype "passive"))
      (node (ref "IC3") (pin "91") (pinfunction "(ADC6/TDO)PF6_91") (pintype "bidirectional"))
    )
    (net (code "77") (name "Net-(ANALOGC-S)") (class "Default")
      (node (ref "ANALOG") (pin "3") (pinfunction "S_3") (pintype "passive"))
      (node (ref "IC3") (pin "92") (pinfunction "(ADC5/TMS)PF5_92") (pintype "bidirectional"))
    )
    (net (code "78") (name "Net-(ANALOGD-S)") (class "Default")
      (node (ref "ANALOG") (pin "4") (pinfunction "S_4") (pintype "passive"))
      (node (ref "IC3") (pin "93") (pinfunction "(ADC4/TCK)PF4_93") (pintype "bidirectional"))
    )
    (net (code "79") (name "Net-(ANALOGE-S)") (class "Default")
      (node (ref "ANALOG") (pin "5") (pinfunction "S_5") (pintype "passive"))
      (node (ref "IC3") (pin "94") (pinfunction "(ADC3)PF3_94") (pintype "bidirectional"))
    )
    (net (code "80") (name "Net-(ANALOGF-S)") (class "Default")
      (node (ref "ANALOG") (pin "6") (pinfunction "S_6") (pintype "passive"))
      (node (ref "IC3") (pin "95") (pinfunction "(ADC2)PF2_95") (pintype "bidirectional"))
    )
    (net (code "81") (name "Net-(ANALOGG-S)") (class "Default")
      (node (ref "ANALOG") (pin "7") (pinfunction "S_7") (pintype "passive"))
      (node (ref "IC3") (pin "96") (pinfunction "(ADC1)PF1_96") (pintype "bidirectional"))
    )
    (net (code "82") (name "Net-(ANALOGH-S)") (class "Default")
      (node (ref "ANALOG") (pin "8") (pinfunction "S_8") (pintype "passive"))
      (node (ref "IC3") (pin "97") (pinfunction "(ADC0)PF0_97") (pintype "bidirectional"))
    )
    (net (code "83") (name "Net-(DBGB-S)") (class "Default")
      (node (ref "DBG") (pin "10") (pinfunction "S_10") (pintype "passive"))
      (node (ref "IC3") (pin "27") (pinfunction "PH7(T4)_27") (pintype "bidirectional"))
    )
    (net (code "84") (name "Net-(DBGF-S)") (class "Default")
      (node (ref "DBG") (pin "5") (pinfunction "S_5") (pintype "passive"))
      (node (ref "IC3") (pin "14") (pinfunction "PH2(XCK2)_14") (pintype "bidirectional"))
    )
    (net (code "85") (name "Net-(F2-Pad2)") (class "Default")
      (node (ref "F2") (pin "2") (pinfunction "2_2") (pintype "passive"))
      (node (ref "U$9") (pin "P$1") (pinfunction "P$1_P$1") (pintype "bidirectional"))
    )
    (net (code "86") (name "Net-(IC3-(CLKO{slash}ICP3{slash}INT7)PE7)") (class "Default")
      (node (ref "IC3") (pin "9") (pinfunction "(CLKO/ICP3/INT7)PE7_9") (pintype "bidirectional"))
      (node (ref "U$21") (pin "2") (pinfunction "K_2") (pintype "bidirectional"))
    )
    (net (code "87") (name "Net-(IC3-(T3{slash}INT6)PE6)") (class "Default")
      (node (ref "IC3") (pin "8") (pinfunction "(T3/INT6)PE6_8") (pintype "bidirectional"))
      (node (ref "U$20") (pin "2") (pinfunction "K_2") (pintype "bidirectional"))
    )
    (net (code "88") (name "Net-(IC3-(XCK0{slash}AIN0)PE2)") (class "Default")
      (node (ref "IC3") (pin "4") (pinfunction "(XCK0/AIN0)PE2_4") (pintype "bidirectional"))
      (node (ref "RN7") (pin "4") (pinfunction "1_4") (pintype "passive"))
    )
    (net (code "89") (name "Net-(IC3-PJ4(PCINT13))") (class "Default")
      (node (ref "IC3") (pin "67") (pinfunction "PJ4(PCINT13)_67") (pintype "bidirectional"))
      (node (ref "U$8") (pin "P$8") (pinfunction "4B_P$8") (pintype "bidirectional"))
    )
    (net (code "90") (name "Net-(IC3-PJ5(PCINT14))") (class "Default")
      (node (ref "IC3") (pin "68") (pinfunction "PJ5(PCINT14)_68") (pintype "bidirectional"))
      (node (ref "U$8") (pin "P$7") (pinfunction "3B_P$7") (pintype "bidirectional"))
    )
    (net (code "91") (name "Net-(IC3-PJ6(PCINT15))") (class "Default")
      (node (ref "IC3") (pin "69") (pinfunction "PJ6(PCINT15)_69") (pintype "bidirectional"))
      (node (ref "U$8") (pin "P$6") (pinfunction "2B_P$6") (pintype "bidirectional"))
    )
    (net (code "92") (name "Net-(IC3-PJ7)") (class "Default")
      (node (ref "IC3") (pin "79") (pinfunction "PJ7_79") (pintype "bidirectional"))
      (node (ref "U$8") (pin "P$5") (pinfunction "1B_P$5") (pintype "bidirectional"))
    )
    (net (code "93") (name "Net-(IC3-PK0(ADC8{slash}PCINT16))") (class "Default")
      (node (ref "IC3") (pin "89") (pinfunction "PK0(ADC8/PCINT16)_89") (pintype "bidirectional"))
      (node (ref "R13") (pin "1") (pinfunction "1_1") (pintype "passive"))
      (node (ref "R14") (pin "2") (pinfunction "2_2") (pintype "passive"))
    )
    (net (code "94") (name "Net-(IC3-PK1(ADC9{slash}PCINT17))") (class "Default")
      (node (ref "IC3") (pin "88") (pinfunction "PK1(ADC9/PCINT17)_88") (pintype "bidirectional"))
      (node (ref "R15") (pin "1") (pinfunction "1_1") (pintype "passive"))
      (node (ref "R16") (pin "2") (pinfunction "2_2") (pintype "passive"))
    )
    (net (code "95") (name "Net-(RN4C-1)") (class "Default")
      (node (ref "RN4") (pin "3") (pinfunction "1_3") (pintype "passive"))
      (node (ref "TX") (pin "A") (pinfunction "A_A") (pintype "passive"))
    )
    (net (code "96") (name "Net-(RN4D-1)") (class "Default")
      (node (ref "RN4") (pin "4") (pinfunction "1_4") (pintype "passive"))
      (node (ref "RX") (pin "A") (pinfunction "A_A") (pintype "passive"))
    )
    (net (code "97") (name "Net-(RN6B-1)") (class "Default")
      (node (ref "RN6") (pin "2") (pinfunction "1_2") (pintype "passive"))
      (node (ref "U$8") (pin "P$3") (pinfunction "3A_P$3") (pintype "bidirectional"))
    )
    (net (code "98") (name "Net-(RN6C-1)") (class "Default")
      (node (ref "RN6") (pin "3") (pinfunction "1_3") (pintype "passive"))
      (node (ref "U$8") (pin "P$2") (pinfunction "2A_P$2") (pintype "bidirectional"))
    )
    (net (code "99") (name "Net-(RN6D-1)") (class "Default")
      (node (ref "RN6") (pin "4") (pinfunction "1_4") (pintype "passive"))
      (node (ref "U$8") (pin "P$1") (pinfunction "1A_P$1") (pintype "bidirectional"))
    )
    (net (code "100") (name "Net-(RN7A-2)") (class "Default")
      (node (ref "RN7") (pin "8") (pinfunction "2_8") (pintype "passive"))
      (node (ref "U$18") (pin "P$1") (pinfunction "P$1_P$1") (pintype "bidirectional"))
    )
    (net (code "101") (name "Net-(RN7B-2)") (class "Default")
      (node (ref "RN7") (pin "7") (pinfunction "2_7") (pintype "passive"))
      (node (ref "U$18") (pin "P$2") (pinfunction "P$2_P$2") (pintype "bidirectional"))
    )
    (net (code "102") (name "Net-(RN7C-2)") (class "Default")
      (node (ref "RN7") (pin "6") (pinfunction "2_6") (pintype "passive"))
      (node (ref "U$18") (pin "P$3") (pinfunction "P$3_P$3") (pintype "bidirectional"))
    )
    (net (code "103") (name "Net-(RN7D-2)") (class "Default")
      (node (ref "RN7") (pin "5") (pinfunction "2_5") (pintype "passive"))
      (node (ref "U$19") (pin "P$2") (pinfunction "K_P$2") (pintype "bidirectional"))
    )
    (net (code "104") (name "Net-(RN8C-1)") (class "Default")
      (node (ref "RN8") (pin "3") (pinfunction "1_3") (pintype "passive"))
      (node (ref "U$21") (pin "1") (pinfunction "A_1") (pintype "bidirectional"))
    )
    (net (code "105") (name "Net-(RN8D-1)") (class "Default")
      (node (ref "RN8") (pin "4") (pinfunction "1_4") (pintype "passive"))
      (node (ref "U$20") (pin "1") (pinfunction "A_1") (pintype "bidirectional"))
    )
    (net (code "106") (name "Net-(SOL-5VA-S)") (class "Default")
      (node (ref "R12") (pin "1") (pinfunction "1_1") (pintype "passive"))
      (node (ref "SOL-5V") (pin "1") (pinfunction "S_1") (pintype "passive"))
      (node (ref "U$17") (pin "2") (pinfunction "K_2") (pintype "bidirectional"))
    )
    (net (code "107") (name "Net-(SOL-5VB-S)") (class "Default")
      (node (ref "SOL-5V") (pin "2") (pinfunction "S_2") (pintype "passive"))
      (node (ref "U$15") (pin "P$6") (pinfunction "D_P$6") (pintype "bidirectional"))
      (node (ref "U$17") (pin "1") (pinfunction "A_1") (pintype "bidirectional"))
    )
    (net (code "108") (name "Net-(SOL-12VA-S)") (class "Default")
      (node (ref "R11") (pin "1") (pinfunction "1_1") (pintype "passive"))
      (node (ref "SOL-12V") (pin "1") (pinfunction "S_1") (pintype "passive"))
      (node (ref "U$16") (pin "2") (pinfunction "K_2") (pintype "bidirectional"))
    )
    (net (code "109") (name "Net-(SOL-12VB-S)") (class "Default")
      (node (ref "SOL-12V") (pin "2") (pinfunction "S_2") (pintype "passive"))
      (node (ref "U$15") (pin "P$3") (pinfunction "D_P$3") (pintype "bidirectional"))
      (node (ref "U$16") (pin "1") (pinfunction "A_1") (pintype "bidirectional"))
    )
    (net (code "110") (name "Net-(SR1B-S)") (class "Default")
      (node (ref "SR1") (pin "2") (pinfunction "S_2") (pintype "passive"))
      (node (ref "SV1") (pin "2") (pinfunction "2_2") (pintype "passive"))
    )
    (net (code "111") (name "Net-(SRV2B-S)") (class "Default")
      (node (ref "SRV2") (pin "2") (pinfunction "S_2") (pintype "passive"))
      (node (ref "SV2") (pin "2") (pinfunction "2_2") (pintype "passive"))
    )
    (net (code "112") (name "Net-(SRV3B-S)") (class "Default")
      (node (ref "SRV3") (pin "2") (pinfunction "S_2") (pintype "passive"))
      (node (ref "SV3") (pin "2") (pinfunction "2_2") (pintype "passive"))
    )
    (net (code "113") (name "Net-(STP-A1A-S)") (class "Default")
      (node (ref "STP-A1") (pin "1") (pinfunction "S_1") (pintype "passive"))
      (node (ref "STP1") (pin "5") (pinfunction "AOUT1_5") (pintype "bidirectional"))
    )
    (net (code "114") (name "Net-(STP-A1B-S)") (class "Default")
      (node (ref "STP-A1") (pin "2") (pinfunction "S_2") (pintype "passive"))
      (node (ref "STP1") (pin "7") (pinfunction "AOUT2_7") (pintype "bidirectional"))
    )
    (net (code "115") (name "Net-(STP-AA-S)") (class "Default")
      (node (ref "STP-A") (pin "1") (pinfunction "S_1") (pintype "passive"))
      (node (ref "STP2") (pin "5") (pinfunction "AOUT1_5") (pintype "bidirectional"))
    )
    (net (code "116") (name "Net-(STP-AB-S)") (class "Default")
      (node (ref "STP-A") (pin "2") (pinfunction "S_2") (pintype "passive"))
      (node (ref "STP2") (pin "7") (pinfunction "AOUT2_7") (pintype "bidirectional"))
    )
    (net (code "117") (name "Net-(STP-B1A-S)") (class "Default")
      (node (ref "STP-B1") (pin "1") (pinfunction "S_1") (pintype "passive"))
      (node (ref "STP1") (pin "10") (pinfunction "BOUT1_10") (pintype "bidirectional"))
    )
    (net (code "118") (name "Net-(STP-B1B-S)") (class "Default")
      (node (ref "STP-B1") (pin "2") (pinfunction "S_2") (pintype "passive"))
      (node (ref "STP1") (pin "8") (pinfunction "BOUT2_8") (pintype "bidirectional"))
    )
    (net (code "119") (name "Net-(STP-BA-S)") (class "Default")
      (node (ref "STP-B") (pin "1") (pinfunction "S_1") (pintype "passive"))
      (node (ref "STP2") (pin "10") (pinfunction "BOUT1_10") (pintype "bidirectional"))
    )
    (net (code "120") (name "Net-(STP-BB-S)") (class "Default")
      (node (ref "STP-B") (pin "2") (pinfunction "S_2") (pintype "passive"))
      (node (ref "STP2") (pin "8") (pinfunction "BOUT2_8") (pintype "bidirectional"))
    )
    (net (code "121") (name "Net-(STP1-AVREF)") (class "Default")
      (node (ref "R1") (pin "1") (pinfunction "1_1") (pintype "passive"))
      (node (ref "R3") (pin "1") (pinfunction "1_1") (pintype "passive"))
      (node (ref "STP1") (pin "12") (pinfunction "AVREF_12") (pintype "bidirectional"))
      (node (ref "STP1") (pin "13") (pinfunction "BVREF_13") (pintype "bidirectional"))
    )
    (net (code "122") (name "Net-(STP1-CP1)") (class "Default")
      (node (ref "C15") (pin "1") (pinfunction "1_1") (pintype "passive"))
      (node (ref "STP1") (pin "1") (pinfunction "CP1_1") (pintype "power_in"))
    )
    (net (code "123") (name "Net-(STP1-CP2)") (class "Default")
      (node (ref "C15") (pin "2") (pinfunction "2_2") (pintype "passive"))
      (node (ref "STP1") (pin "2") (pinfunction "CP2_2") (pintype "power_in"))
    )
    (net (code "124") (name "Net-(STP1-ISENA)") (class "Default")
      (node (ref "R20") (pin "2") (pinfunction "2_2") (pintype "passive"))
      (node (ref "STP1") (pin "6") (pinfunction "ISENA_6") (pintype "bidirectional"))
    )
    (net (code "125") (name "Net-(STP1-ISENB)") (class "Default")
      (node (ref "R19") (pin "2") (pinfunction "2_2") (pintype "passive"))
      (node (ref "STP1") (pin "9") (pinfunction "ISENB_9") (pintype "bidirectional"))
    )
    (net (code "126") (name "Net-(STP1-V3P3OUT)") (class "Default")
      (node (ref "C20") (pin "1") (pinfunction "1_1") (pintype "passive"))
      (node (ref "R3") (pin "2") (pinfunction "2_2") (pintype "passive"))
      (node (ref "STP1") (pin "15") (pinfunction "V3P3OUT_15") (pintype "power_in"))
    )
    (net (code "127") (name "Net-(STP2-AVREF)") (class "Default")
      (node (ref "R6") (pin "1") (pinfunction "1_1") (pintype "passive"))
      (node (ref "R8") (pin "1") (pinfunction "1_1") (pintype "passive"))
      (node (ref "STP2") (pin "12") (pinfunction "AVREF_12") (pintype "bidirectional"))
      (node (ref "STP2") (pin "13") (pinfunction "BVREF_13") (pintype "bidirectional"))
    )
    (net (code "128") (name "Net-(STP2-CP1)") (class "Default")
      (node (ref "C11") (pin "1") (pinfunction "1_1") (pintype "passive"))
      (node (ref "STP2") (pin "1") (pinfunction "CP1_1") (pintype "power_in"))
    )
    (net (code "129") (name "Net-(STP2-CP2)") (class "Default")
      (node (ref "C11") (pin "2") (pinfunction "2_2") (pintype "passive"))
      (node (ref "STP2") (pin "2") (pinfunction "CP2_2") (pintype "power_in"))
    )
    (net (code "130") (name "Net-(STP2-ISENA)") (class "Default")
      (node (ref "R21") (pin "2") (pinfunction "2_2") (pintype "passive"))
      (node (ref "STP2") (pin "6") (pinfunction "ISENA_6") (pintype "bidirectional"))
    )
    (net (code "131") (name "Net-(STP2-ISENB)") (class "Default")
      (node (ref "R22") (pin "2") (pinfunction "2_2") (pintype "passive"))
      (node (ref "STP2") (pin "9") (pinfunction "ISENB_9") (pintype "bidirectional"))
    )
    (net (code "132") (name "Net-(STP2-V3P3OUT)") (class "Default")
      (node (ref "C13") (pin "1") (pinfunction "1_1") (pintype "passive"))
      (node (ref "R8") (pin "2") (pinfunction "2_2") (pintype "passive"))
      (node (ref "STP2") (pin "15") (pinfunction "V3P3OUT_15") (pintype "power_in"))
    )
    (net (code "133") (name "Net-(U$8-4A)") (class "Default")
      (node (ref "RN6") (pin "1") (pinfunction "1_1") (pintype "passive"))
      (node (ref "U$8") (pin "P$4") (pinfunction "4A_P$4") (pintype "bidirectional"))
    )
    (net (code "134") (name "Net-(U$15A-G)") (class "Default")
      (node (ref "R14") (pin "1") (pinfunction "1_1") (pintype "passive"))
      (node (ref "U$15") (pin "P$2") (pinfunction "G_P$2") (pintype "bidirectional"))
    )
    (net (code "135") (name "Net-(U$15B-G)") (class "Default")
      (node (ref "R16") (pin "1") (pinfunction "1_1") (pintype "passive"))
      (node (ref "U$15") (pin "P$5") (pinfunction "G_P$5") (pintype "bidirectional"))
    )
    (net (code "136") (name "unconnected-(IC3-(AD0)PA0-Pad78)") (class "Default")
      (node (ref "IC3") (pin "78") (pinfunction "(AD0)PA0_78") (pintype "bidirectional"))
    )
    (net (code "137") (name "unconnected-(IC3-(AD1)PA1-Pad77)") (class "Default")
      (node (ref "IC3") (pin "77") (pinfunction "(AD1)PA1_77") (pintype "bidirectional"))
    )
    (net (code "138") (name "unconnected-(IC3-(AD2)PA2-Pad76)") (class "Default")
      (node (ref "IC3") (pin "76") (pinfunction "(AD2)PA2_76") (pintype "bidirectional"))
    )
    (net (code "139") (name "unconnected-(IC3-(AD3)PA3-Pad75)") (class "Default")
      (node (ref "IC3") (pin "75") (pinfunction "(AD3)PA3_75") (pintype "bidirectional"))
    )
    (net (code "140") (name "unconnected-(IC3-(AD4)PA4-Pad74)") (class "Default")
      (node (ref "IC3") (pin "74") (pinfunction "(AD4)PA4_74") (pintype "bidirectional"))
    )
    (net (code "141") (name "unconnected-(IC3-(ICP1)PD4-Pad47)") (class "Default")
      (node (ref "IC3") (pin "47") (pinfunction "(ICP1)PD4_47") (pintype "bidirectional"))
    )
    (net (code "142") (name "unconnected-(IC3-(OC0B)PG5-Pad1)") (class "Default")
      (node (ref "IC3") (pin "1") (pinfunction "(OC0B)PG5_1") (pintype "bidirectional"))
    )
    (net (code "143") (name "unconnected-(IC3-(OC2A{slash}PCINT4)PB4-Pad23)") (class "Default")
      (node (ref "IC3") (pin "23") (pinfunction "(OC2A/PCINT4)PB4_23") (pintype "bidirectional"))
    )
    (net (code "144") (name "unconnected-(IC3-(RXD1{slash}INT2)PD2-Pad45)") (class "Default")
      (node (ref "IC3") (pin "45") (pinfunction "(RXD1/INT2)PD2_45") (pintype "bidirectional"))
    )
    (net (code "145") (name "unconnected-(IC3-(SCL{slash}INT0)PD0-Pad43)") (class "Default")
      (node (ref "IC3") (pin "43") (pinfunction "(SCL/INT0)PD0_43") (pintype "bidirectional"))
    )
    (net (code "146") (name "unconnected-(IC3-(SDA{slash}INT1)PD1-Pad44)") (class "Default")
      (node (ref "IC3") (pin "44") (pinfunction "(SDA/INT1)PD1_44") (pintype "bidirectional"))
    )
    (net (code "147") (name "unconnected-(IC3-(SS{slash}PCINT0)PB0-Pad19)") (class "Default")
      (node (ref "IC3") (pin "19") (pinfunction "(SS/PCINT0)PB0_19") (pintype "bidirectional"))
    )
    (net (code "148") (name "unconnected-(IC3-(T0)PD7-Pad50)") (class "Default")
      (node (ref "IC3") (pin "50") (pinfunction "(T0)PD7_50") (pintype "bidirectional"))
    )
    (net (code "149") (name "unconnected-(IC3-(T1)PD6-Pad49)") (class "Default")
      (node (ref "IC3") (pin "49") (pinfunction "(T1)PD6_49") (pintype "bidirectional"))
    )
    (net (code "150") (name "unconnected-(IC3-(TOSC1)PG4-Pad29)") (class "Default")
      (node (ref "IC3") (pin "29") (pinfunction "(TOSC1)PG4_29") (pintype "bidirectional"))
    )
    (net (code "151") (name "unconnected-(IC3-(TXD1{slash}INT3)PD3-Pad46)") (class "Default")
      (node (ref "IC3") (pin "46") (pinfunction "(TXD1/INT3)PD3_46") (pintype "bidirectional"))
    )
    (net (code "152") (name "unconnected-(IC3-(XCK1)PD5-Pad48)") (class "Default")
      (node (ref "IC3") (pin "48") (pinfunction "(XCK1)PD5_48") (pintype "bidirectional"))
    )
    (net (code "153") (name "unconnected-(IC3-PJ0(RXD3{slash}PCINT9)-Pad63)") (class "Default")
      (node (ref "IC3") (pin "63") (pinfunction "PJ0(RXD3/PCINT9)_63") (pintype "bidirectional"))
    )
    (net (code "154") (name "unconnected-(IC3-PJ1(TXD3{slash}PCINT10)-Pad64)") (class "Default")
      (node (ref "IC3") (pin "64") (pinfunction "PJ1(TXD3/PCINT10)_64") (pintype "bidirectional"))
    )
    (net (code "155") (name "unconnected-(IC3-PJ2(XCK3{slash}PCINT11)-Pad65)") (class "Default")
      (node (ref "IC3") (pin "65") (pinfunction "PJ2(XCK3/PCINT11)_65") (pintype "bidirectional"))
    )
    (net (code "156") (name "unconnected-(IC3-PJ3(PCINT12)-Pad66)") (class "Default")
      (node (ref "IC3") (pin "66") (pinfunction "PJ3(PCINT12)_66") (pintype "bidirectional"))
    )
    (net (code "157") (name "unconnected-(IC3-PK2(ADC10{slash}PCINT18)-Pad87)") (class "Default")
      (node (ref "IC3") (pin "87") (pinfunction "PK2(ADC10/PCINT18)_87") (pintype "bidirectional"))
    )
    (net (code "158") (name "unconnected-(IC3-PK3(ADC11{slash}PCINT19)-Pad86)") (class "Default")
      (node (ref "IC3") (pin "86") (pinfunction "PK3(ADC11/PCINT19)_86") (pintype "bidirectional"))
    )
    (net (code "159") (name "unconnected-(IC3-PK4(ADC12{slash}PCINT20)-Pad85)") (class "Default")
      (node (ref "IC3") (pin "85") (pinfunction "PK4(ADC12/PCINT20)_85") (pintype "bidirectional"))
    )
    (net (code "160") (name "unconnected-(IC3-PK5(ADC13{slash}PCINT21)-Pad84)") (class "Default")
      (node (ref "IC3") (pin "84") (pinfunction "PK5(ADC13/PCINT21)_84") (pintype "bidirectional"))
    )
    (net (code "161") (name "unconnected-(IC3-PK6(ADC14{slash}PCINT22)-Pad83)") (class "Default")
      (node (ref "IC3") (pin "83") (pinfunction "PK6(ADC14/PCINT22)_83") (pintype "bidirectional"))
    )
    (net (code "162") (name "unconnected-(IC3-PK7(ADC15{slash}PCINT23)-Pad82)") (class "Default")
      (node (ref "IC3") (pin "82") (pinfunction "PK7(ADC15/PCINT23)_82") (pintype "bidirectional"))
    )
    (net (code "163") (name "unconnected-(IC3-XTAL1-Pad34)") (class "Default")
      (node (ref "IC3") (pin "34") (pinfunction "XTAL1_34") (pintype "input"))
    )
    (net (code "164") (name "unconnected-(IC3-XTAL2-Pad33)") (class "Default")
      (node (ref "IC3") (pin "33") (pinfunction "XTAL2_33") (pintype "output"))
    )
    (net (code "165") (name "unconnected-(IC4-(AIN0{slash}INT1)PD1-Pad7)") (class "Default")
      (node (ref "IC4") (pin "7") (pinfunction "(AIN0/INT1)PD1_7") (pintype "bidirectional"))
    )
    (net (code "166") (name "unconnected-(IC4-(AIN2{slash}PCINT11)PC2-Pad5)") (class "Default")
      (node (ref "IC4") (pin "5") (pinfunction "(AIN2/PCINT11)PC2_5") (pintype "bidirectional"))
    )
    (net (code "167") (name "unconnected-(IC4-(INT4{slash}ICP1{slash}CLK0)PC7-Pad22)") (class "Default")
      (node (ref "IC4") (pin "22") (pinfunction "(INT4/ICP1/CLK0)PC7_22") (pintype "bidirectional"))
    )
    (net (code "168") (name "unconnected-(IC4-(OC0B{slash}INT0)PD0-Pad6)") (class "Default")
      (node (ref "IC4") (pin "6") (pinfunction "(OC0B/INT0)PD0_6") (pintype "bidirectional"))
    )
    (net (code "169") (name "unconnected-(IC4-(OC1A{slash}PCINT8)PC6-Pad23)") (class "Default")
      (node (ref "IC4") (pin "23") (pinfunction "(OC1A/PCINT8)PC6_23") (pintype "bidirectional"))
    )
    (net (code "170") (name "unconnected-(IC4-(PCINT5)PB5-Pad19)") (class "Default")
      (node (ref "IC4") (pin "19") (pinfunction "(PCINT5)PB5_19") (pintype "bidirectional"))
    )
    (net (code "171") (name "unconnected-(IC4-(PCINT6)PB6-Pad20)") (class "Default")
      (node (ref "IC4") (pin "20") (pinfunction "(PCINT6)PB6_20") (pintype "bidirectional"))
    )
    (net (code "172") (name "unconnected-(IC4-(PCINT7{slash}OC0A{slash}OC1C)PB7-Pad21)") (class "Default")
      (node (ref "IC4") (pin "21") (pinfunction "(PCINT7/OC0A/OC1C)PB7_21") (pintype "bidirectional"))
    )
    (net (code "173") (name "unconnected-(IC4-(PCINT9{slash}OC1B)PC5-Pad25)") (class "Default")
      (node (ref "IC4") (pin "25") (pinfunction "(PCINT9/OC1B)PC5_25") (pintype "bidirectional"))
    )
    (net (code "174") (name "unconnected-(IC4-(PCINT10)PC4-Pad26)") (class "Default")
      (node (ref "IC4") (pin "26") (pinfunction "(PCINT10)PC4_26") (pintype "bidirectional"))
    )
    (net (code "175") (name "unconnected-(IC4-(RTS{slash}AIN5{slash}INT6)PD6-Pad12)") (class "Default")
      (node (ref "IC4") (pin "12") (pinfunction "(RTS/AIN5/INT6)PD6_12") (pintype "bidirectional"))
    )
    (net (code "176") (name "unconnected-(IC4-(SS{slash}PCINT0)PB0-Pad14)") (class "Default")
      (node (ref "IC4") (pin "14") (pinfunction "(SS/PCINT0)PB0_14") (pintype "bidirectional"))
    )
    (net (code "177") (name "unconnected-(IC4-(T1{slash}PCINT4)PB4-Pad18)") (class "Default")
      (node (ref "IC4") (pin "18") (pinfunction "(T1/PCINT4)PB4_18") (pintype "bidirectional"))
    )
    (net (code "178") (name "unconnected-(RN1D-1-Pad4)") (class "Default")
      (node (ref "RN1") (pin "4") (pinfunction "1_4") (pintype "passive"))
    )
    (net (code "179") (name "unconnected-(RN1D-2-Pad5)") (class "Default")
      (node (ref "RN1") (pin "5") (pinfunction "2_5") (pintype "passive"))
    )
    (net (code "180") (name "unconnected-(RN2B-1-Pad2)") (class "Default")
      (node (ref "RN2") (pin "2") (pinfunction "1_2") (pintype "passive"))
    )
    (net (code "181") (name "unconnected-(RN2B-2-Pad7)") (class "Default")
      (node (ref "RN2") (pin "7") (pinfunction "2_7") (pintype "passive"))
    )
    (net (code "182") (name "unconnected-(RN2C-1-Pad3)") (class "Default")
      (node (ref "RN2") (pin "3") (pinfunction "1_3") (pintype "passive"))
    )
    (net (code "183") (name "unconnected-(RN2C-2-Pad6)") (class "Default")
      (node (ref "RN2") (pin "6") (pinfunction "2_6") (pintype "passive"))
    )
    (net (code "184") (name "unconnected-(RN5D-1-Pad4)") (class "Default")
      (node (ref "RN5") (pin "4") (pinfunction "1_4") (pintype "passive"))
    )
    (net (code "185") (name "unconnected-(RN5D-2-Pad5)") (class "Default")
      (node (ref "RN5") (pin "5") (pinfunction "2_5") (pintype "passive"))
    )
    (net (code "186") (name "unconnected-(RN8-Pad1)") (class "Default")
      (node (ref "RN8") (pin "1") (pinfunction "1_1") (pintype "passive"))
    )
    (net (code "187") (name "unconnected-(RN8A-2-Pad8)") (class "Default")
      (node (ref "RN8") (pin "8") (pinfunction "2_8") (pintype "passive"))
    )
    (net (code "188") (name "unconnected-(RN8B-1-Pad2)") (class "Default")
      (node (ref "RN8") (pin "2") (pinfunction "1_2") (pintype "passive"))
    )
    (net (code "189") (name "unconnected-(RN8B-2-Pad7)") (class "Default")
      (node (ref "RN8") (pin "7") (pinfunction "2_7") (pintype "passive"))
    )
  )
)
